# plaits_v10_0603.net
KiCad netlist of a schematic drawn in EAGLE
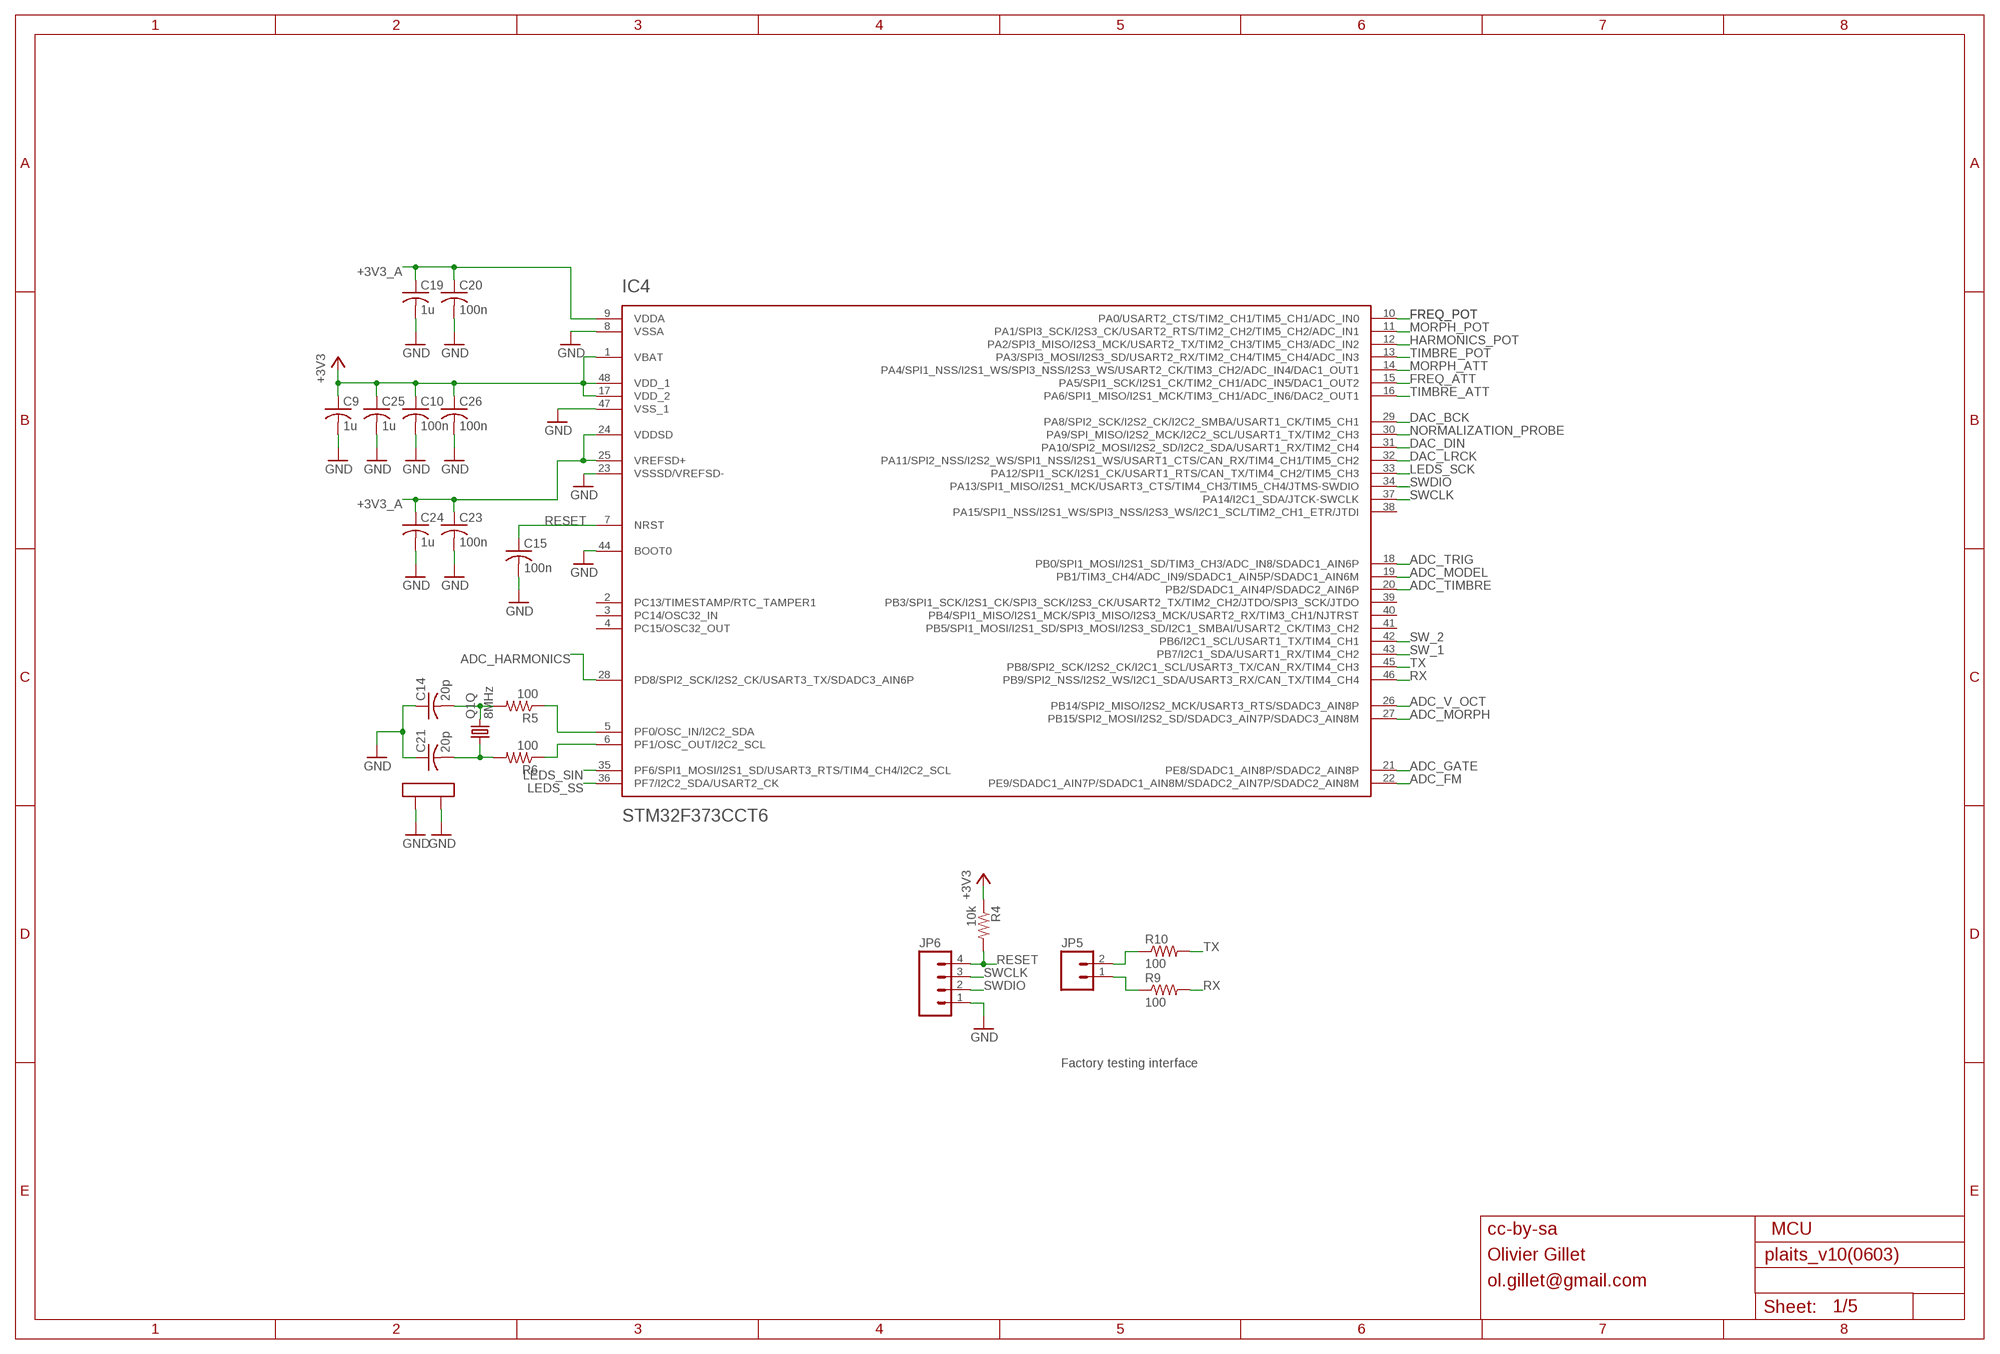
[diagram p0: schematic, sheet 1]
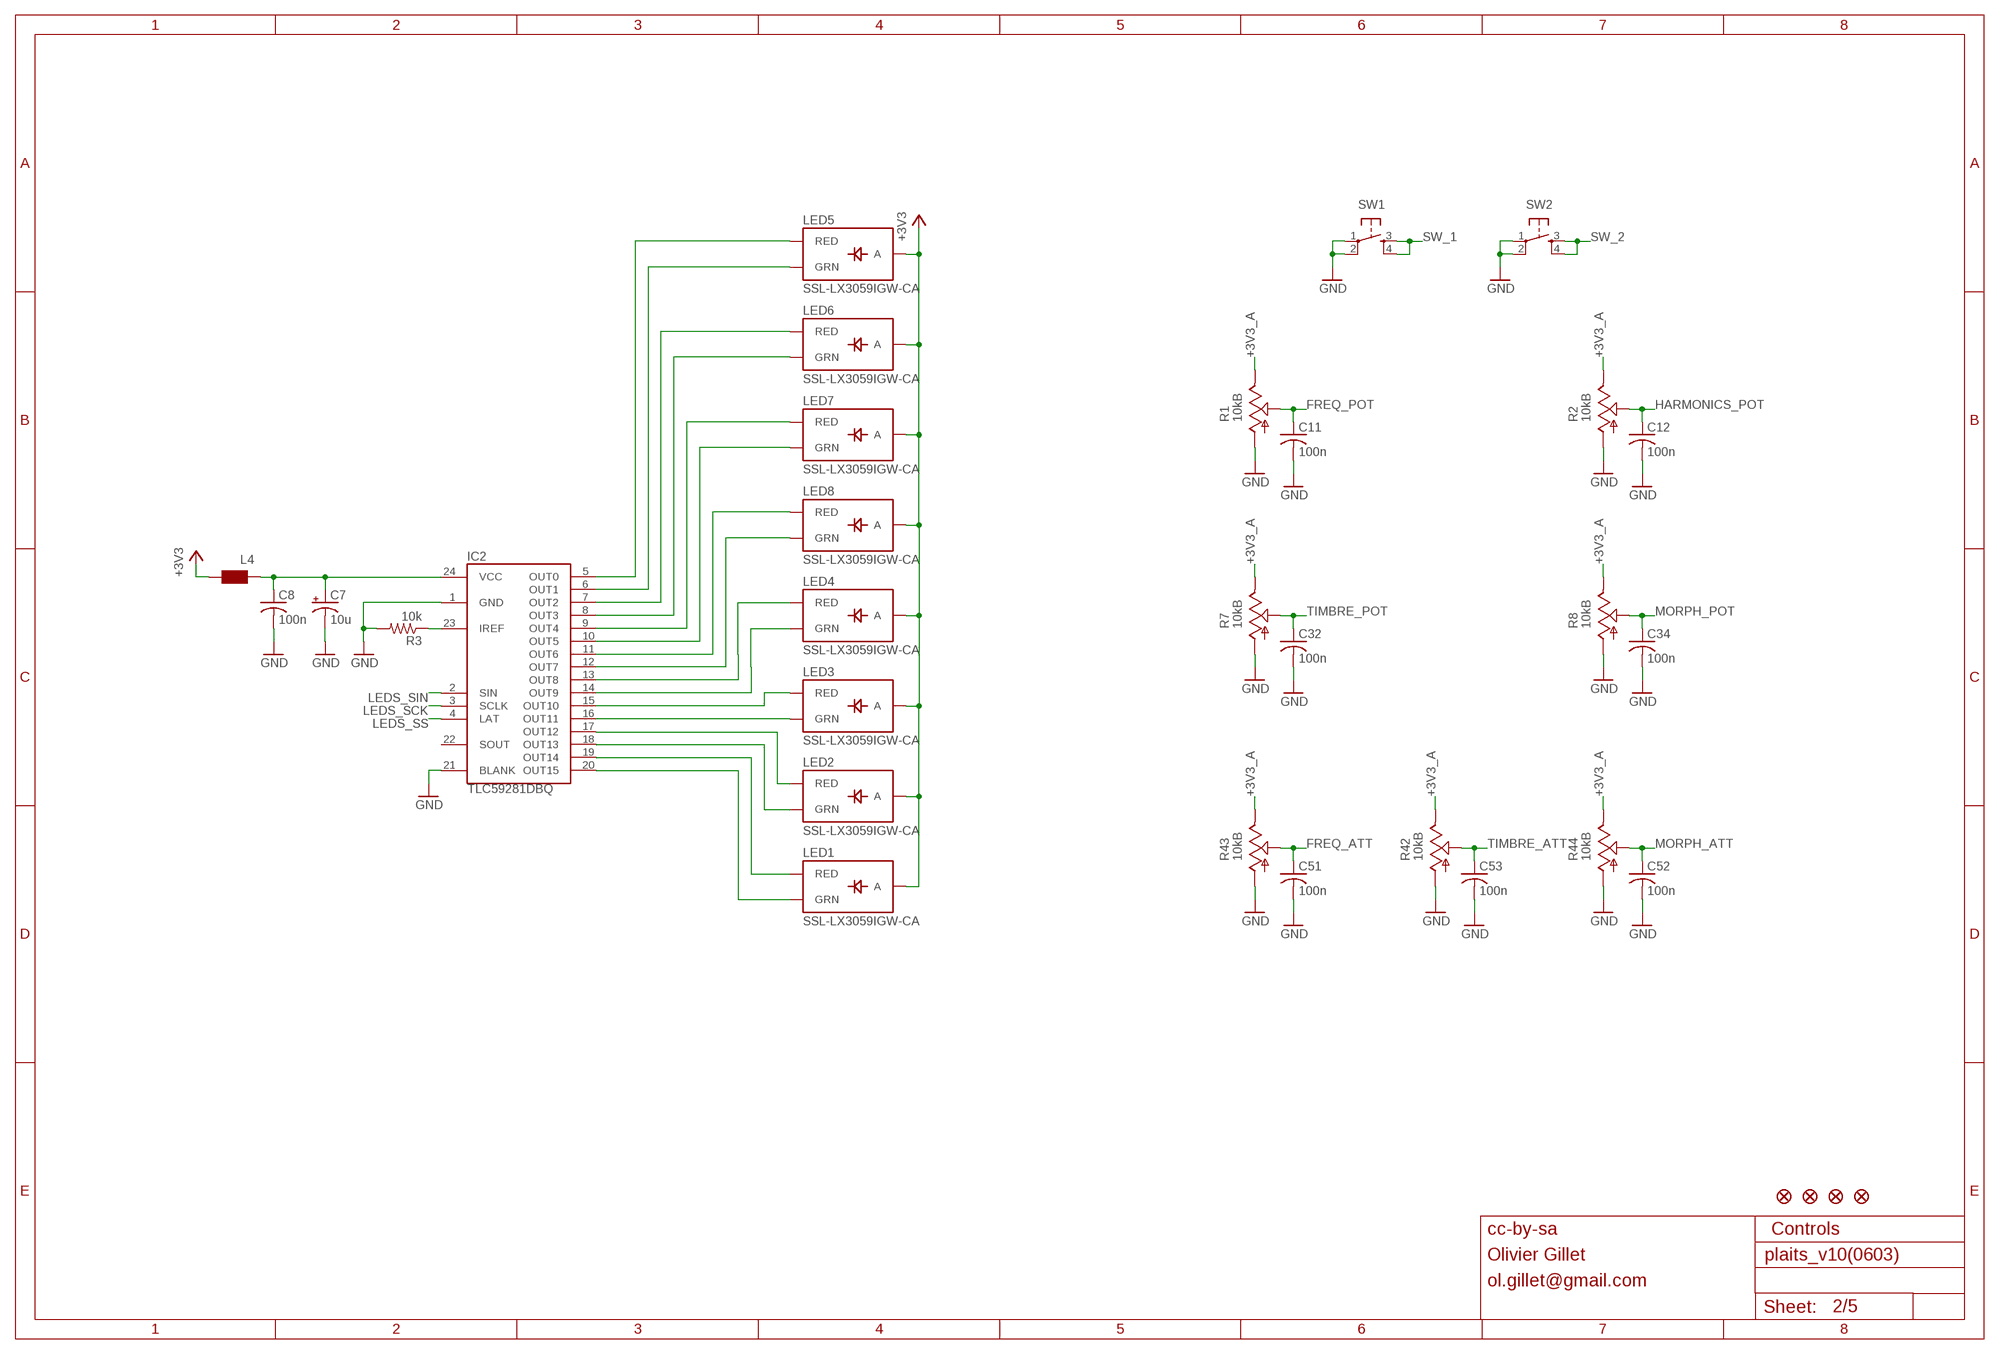
[diagram p1: schematic, sheet 2]
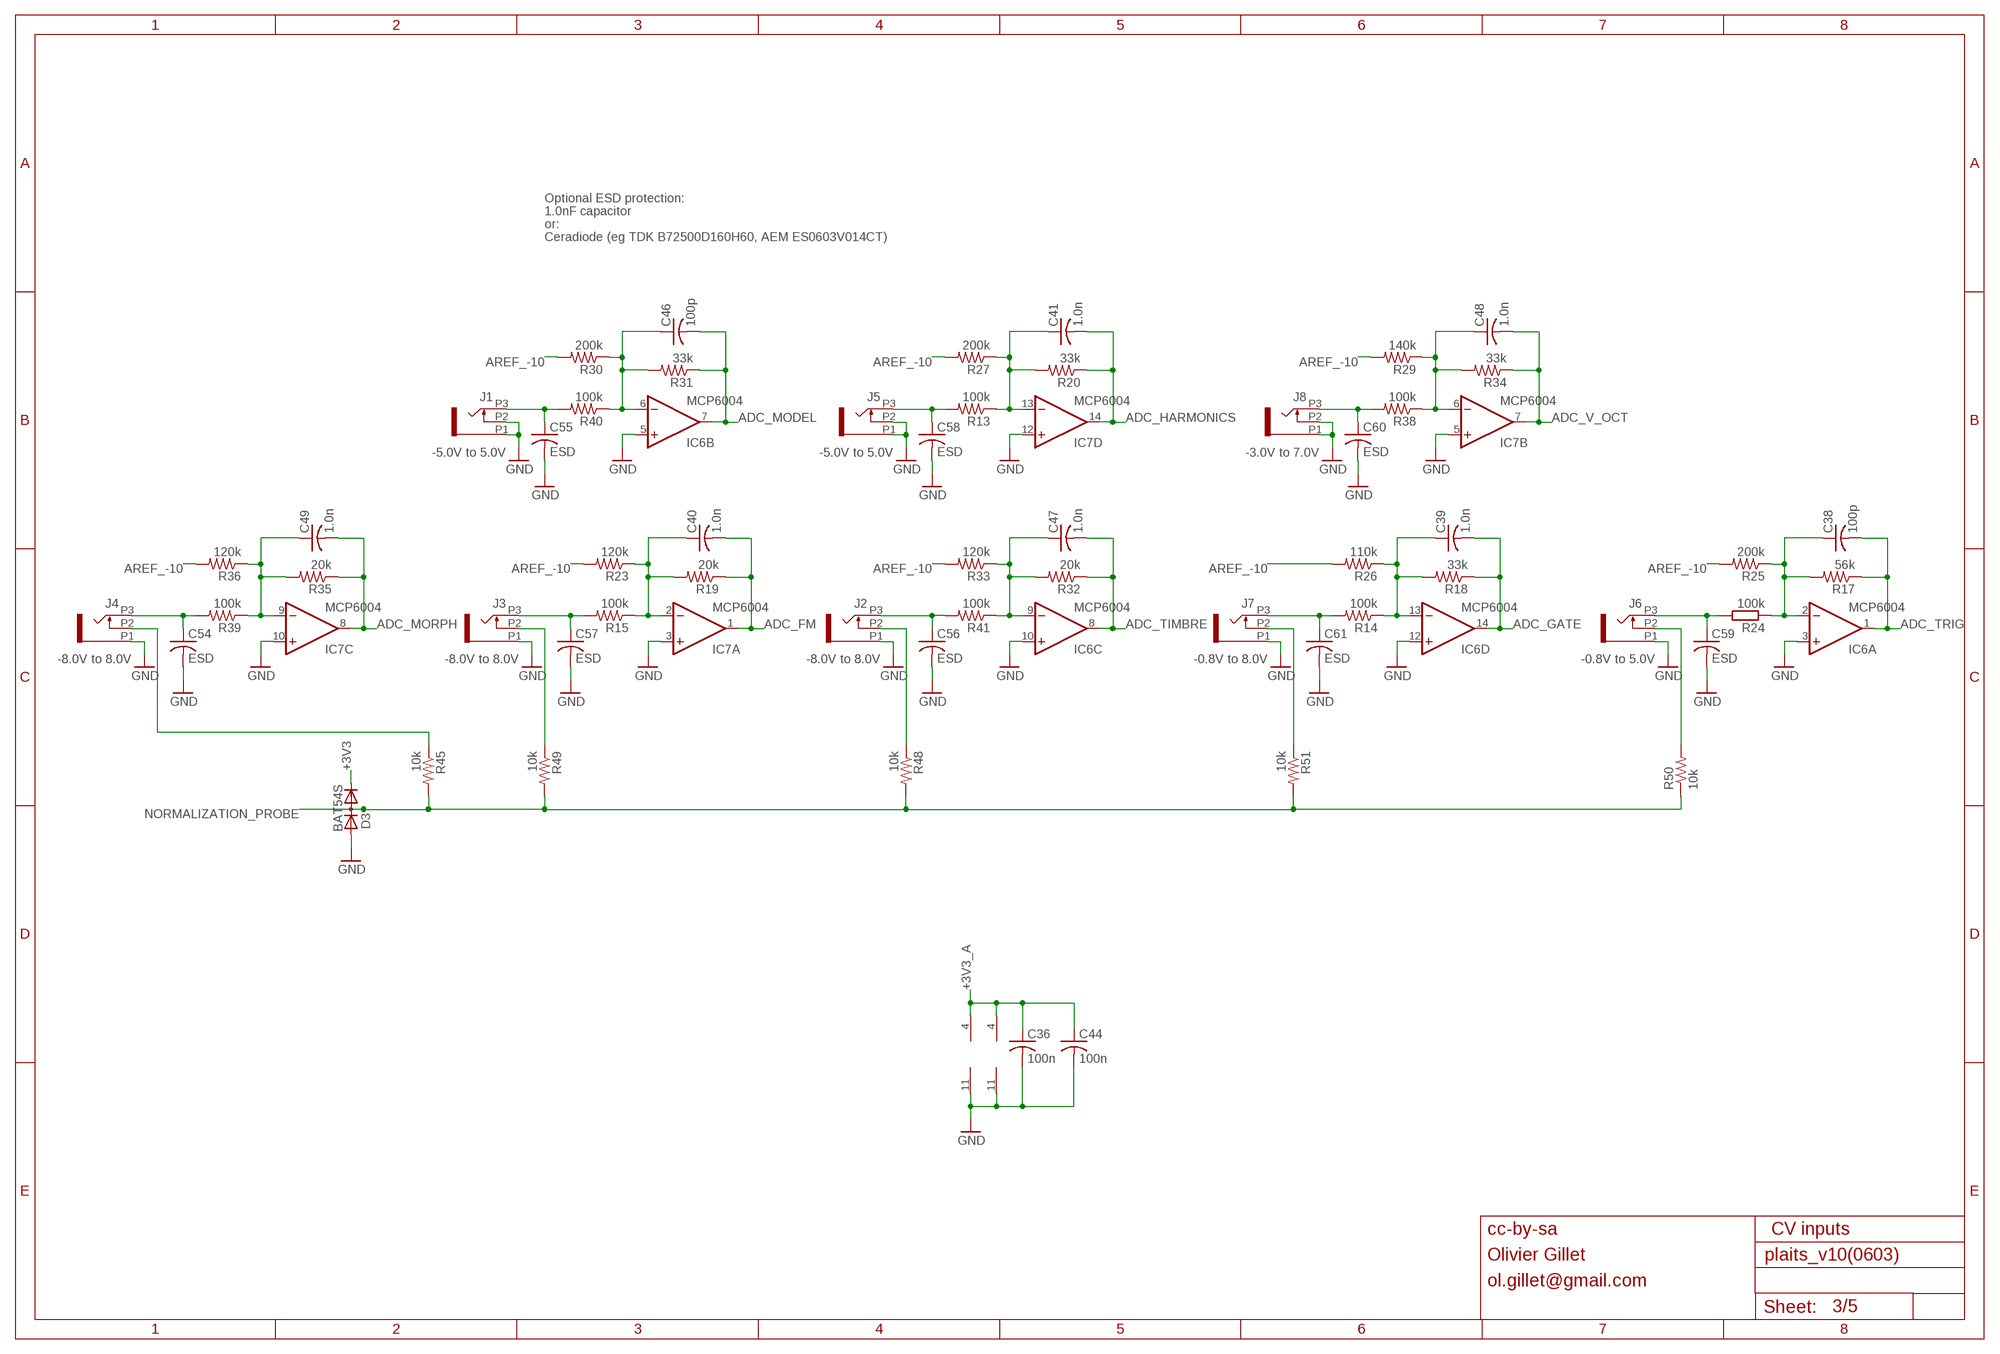
[diagram p2: schematic, sheet 3]
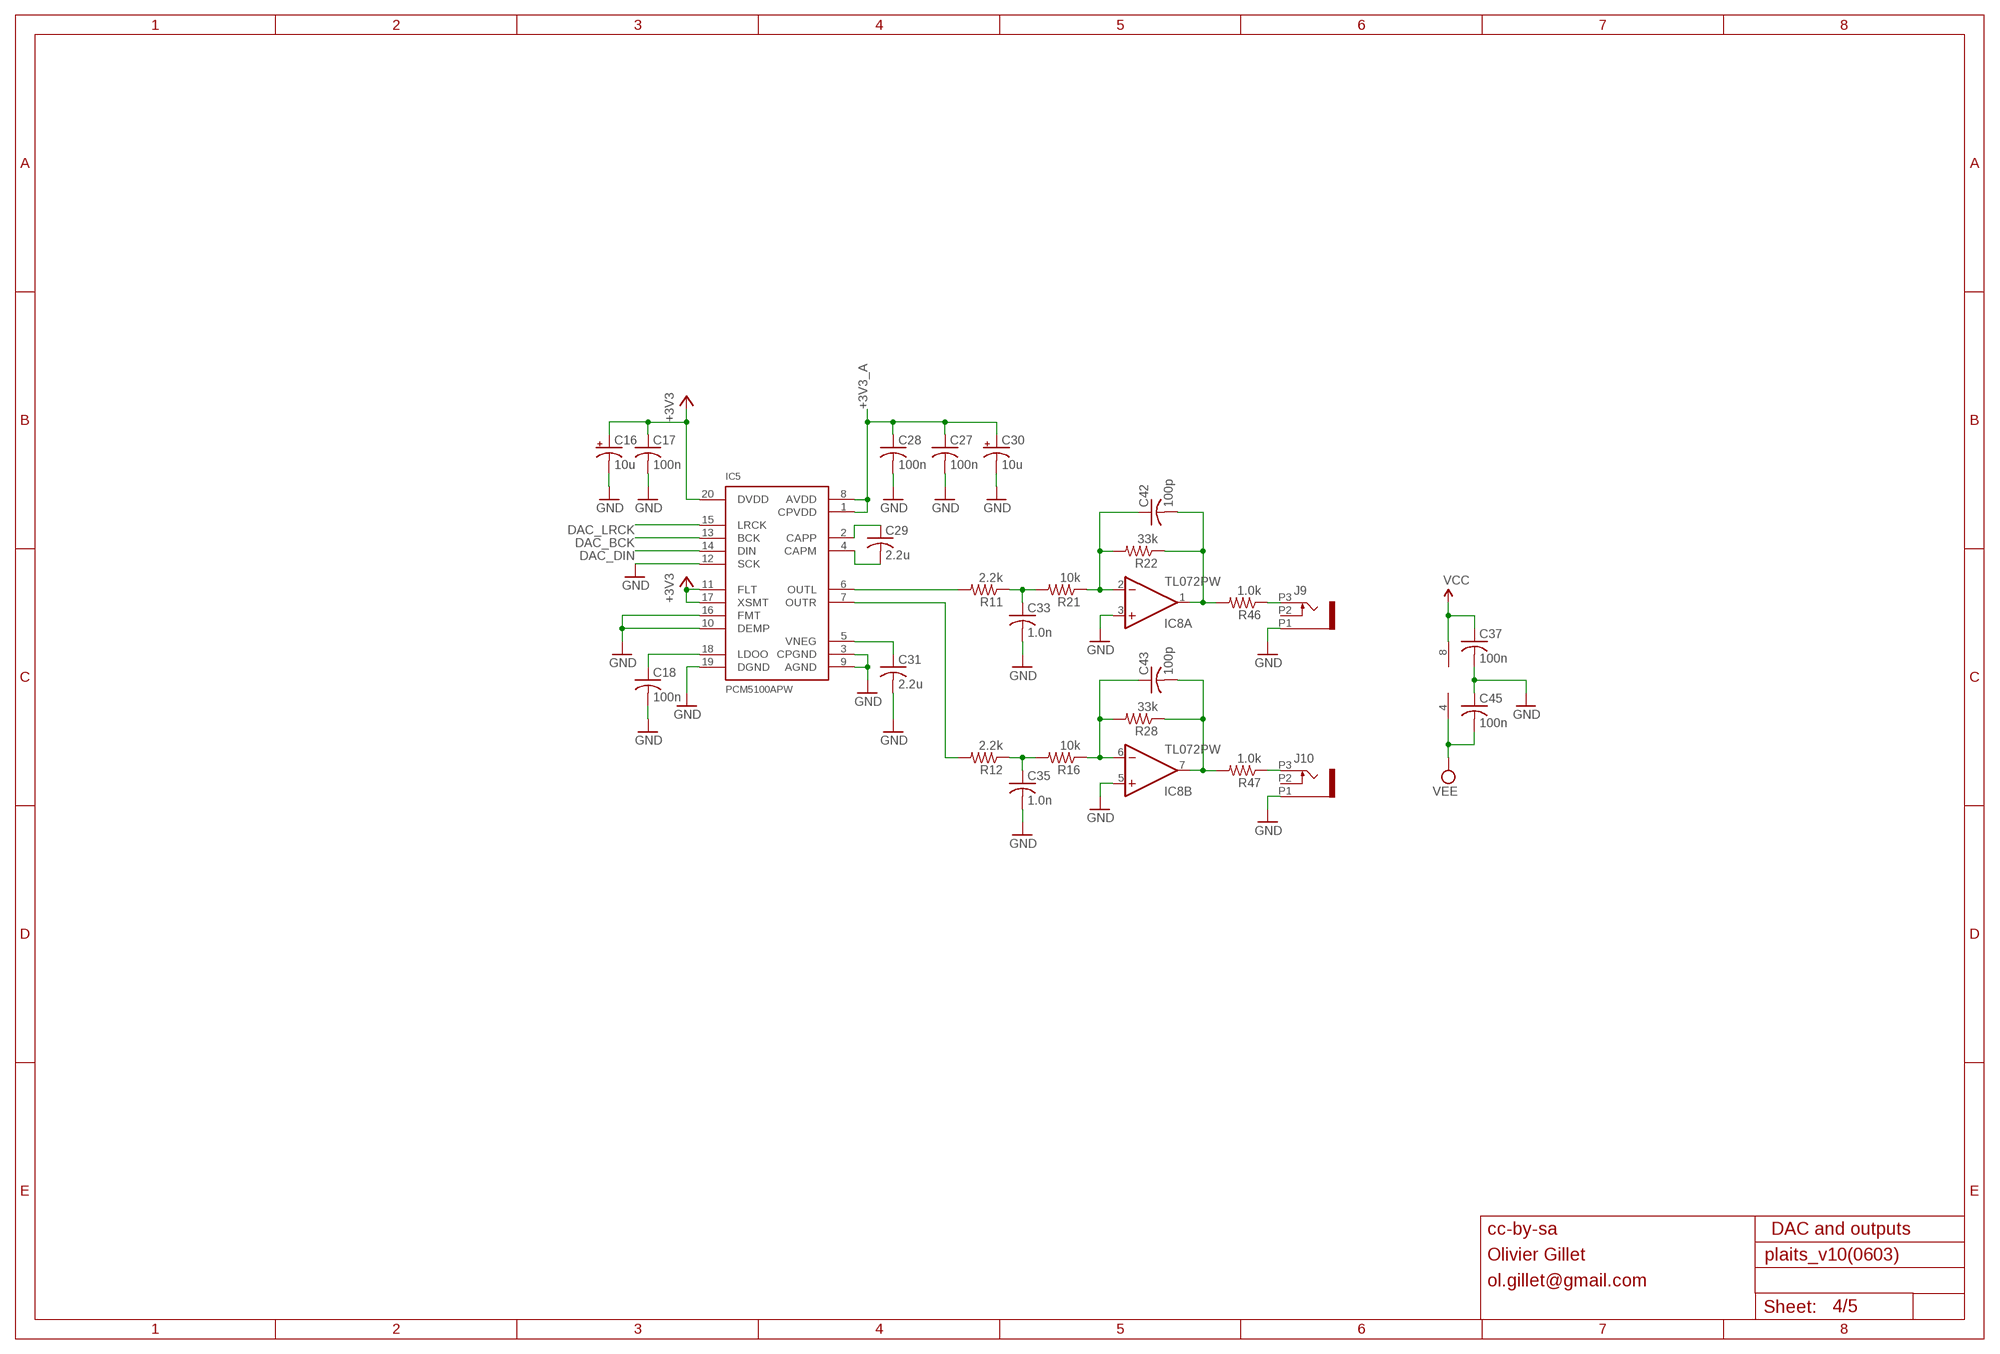
[diagram p3: schematic, sheet 4]
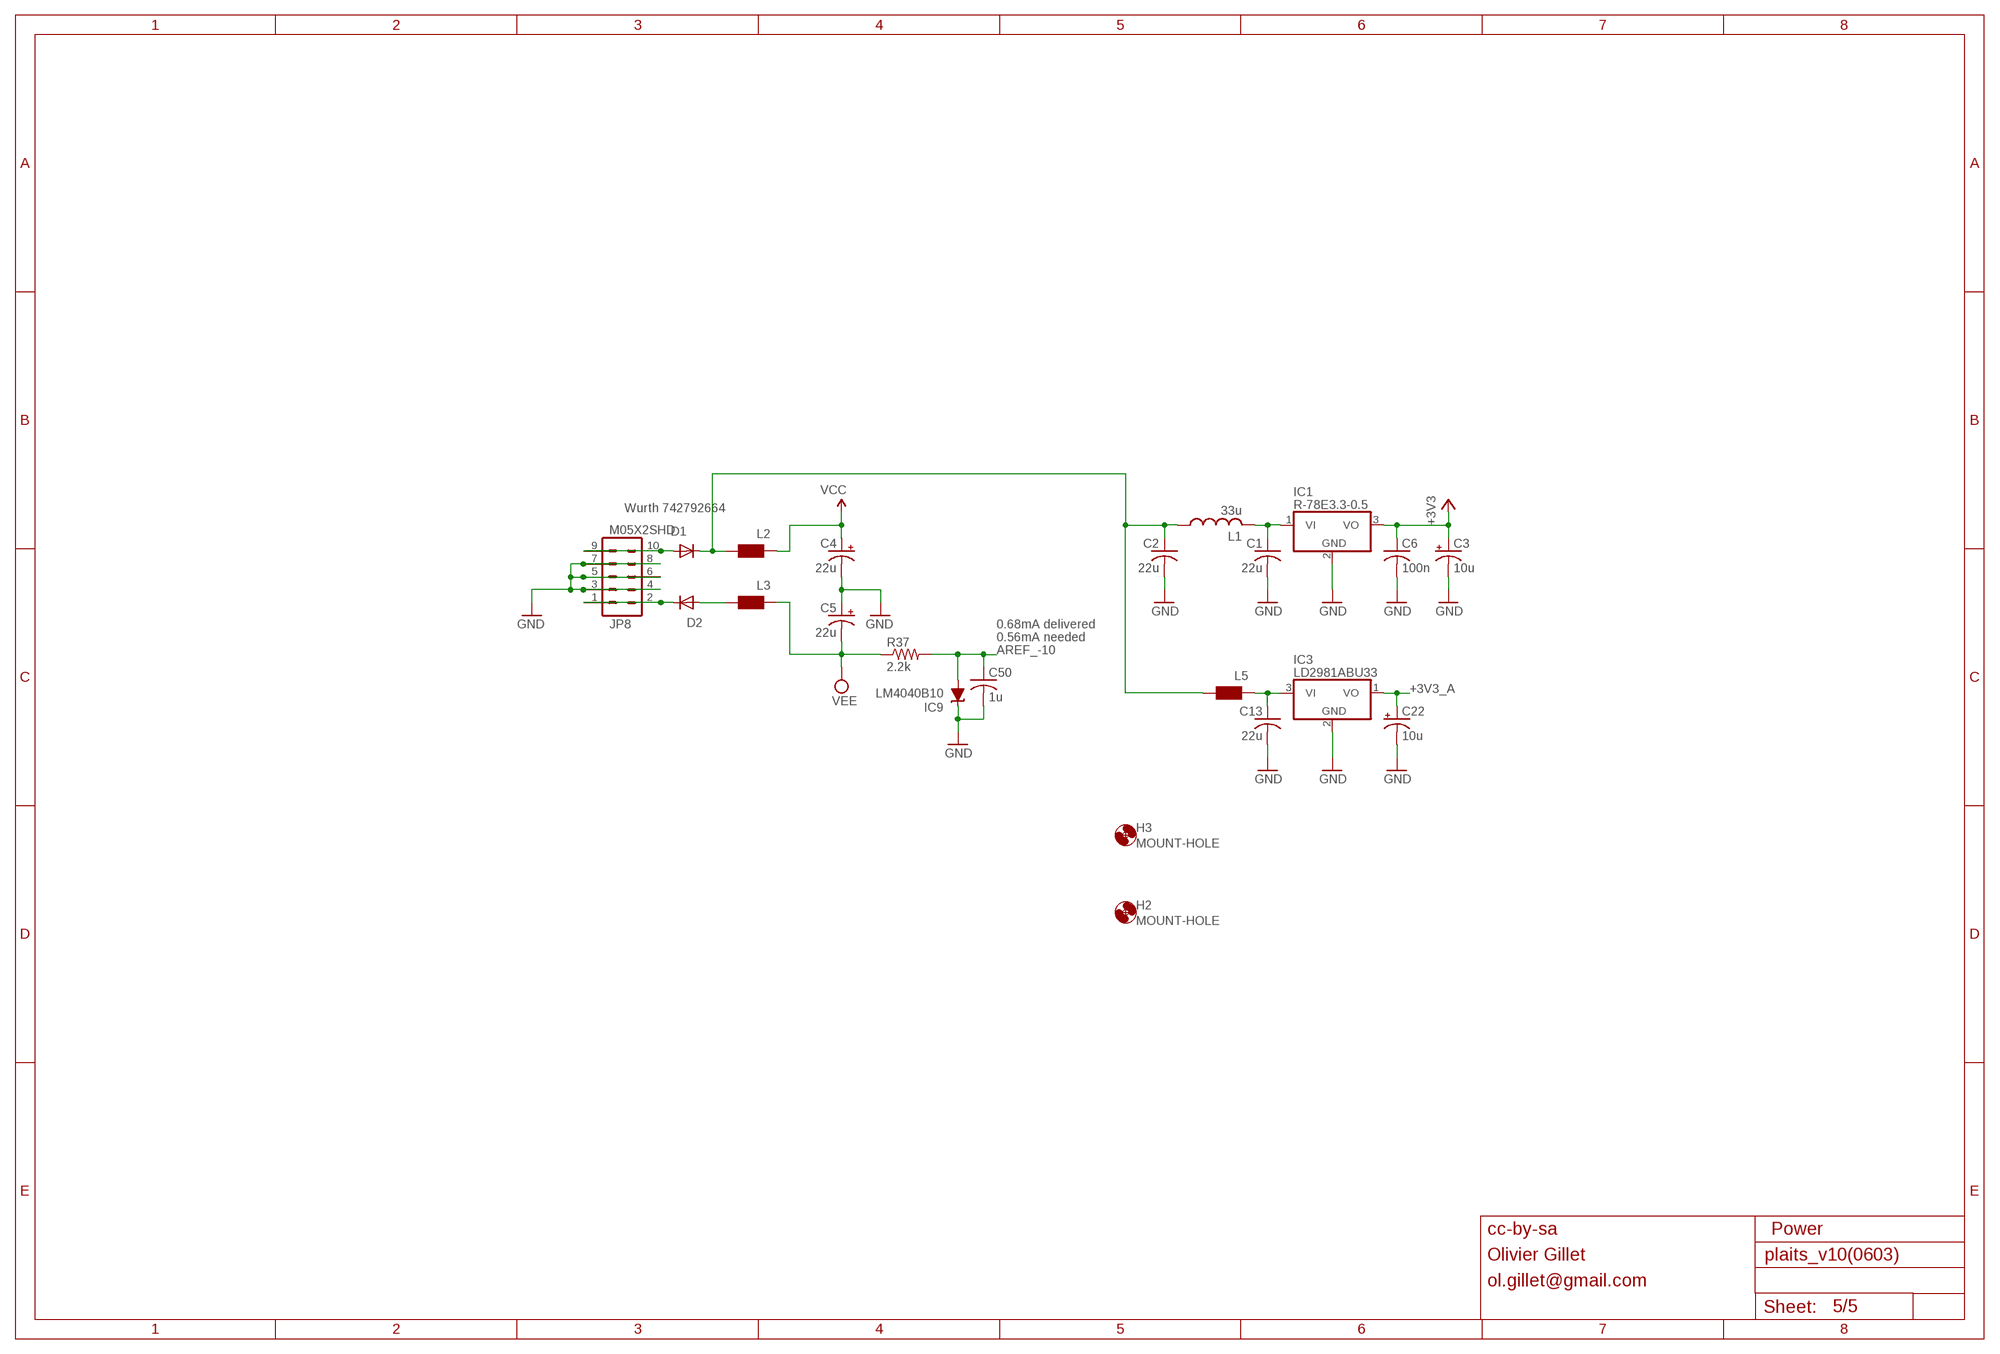
[diagram p4: schematic, sheet 5]

(export (version "E")
  (design (tool "Eeschema 10.0.6"))
  (components
    (comp (ref "C9")
      (value "1u")
      (footprint "eagle-import:C0603")
      (libsource (lib "eagle-import") (part "C-USC0603"))
    )
    (comp (ref "C10")
      (value "100n")
      (footprint "eagle-import:C0603")
      (libsource (lib "eagle-import") (part "C-USC0603"))
    )
    (comp (ref "C14")
      (value "20p")
      (footprint "eagle-import:C0603")
      (libsource (lib "eagle-import") (part "C-USC0603"))
    )
    (comp (ref "C15")
      (value "100n")
      (footprint "eagle-import:C0603")
      (libsource (lib "eagle-import") (part "C-USC0603"))
    )
    (comp (ref "C19")
      (value "1u")
      (footprint "eagle-import:C0603")
      (libsource (lib "eagle-import") (part "C-USC0603"))
    )
    (comp (ref "C20")
      (value "100n")
      (footprint "eagle-import:C0603")
      (libsource (lib "eagle-import") (part "C-USC0603"))
    )
    (comp (ref "C21")
      (value "20p")
      (footprint "eagle-import:C0603")
      (libsource (lib "eagle-import") (part "C-USC0603"))
    )
    (comp (ref "C23")
      (value "100n")
      (footprint "eagle-import:C0603")
      (libsource (lib "eagle-import") (part "C-USC0603"))
    )
    (comp (ref "C24")
      (value "1u")
      (footprint "eagle-import:C0603")
      (libsource (lib "eagle-import") (part "C-USC0603"))
    )
    (comp (ref "C25")
      (value "1u")
      (footprint "eagle-import:C0603")
      (libsource (lib "eagle-import") (part "C-USC0603"))
    )
    (comp (ref "C26")
      (value "100n")
      (footprint "eagle-import:C0603")
      (libsource (lib "eagle-import") (part "C-USC0603"))
    )
    (comp (ref "IC4")
      (value "STM32F373CCT6")
      (footprint "eagle-import:LQFP48")
      (libsource (lib "eagle-import") (part "STM32F373C"))
    )
    (comp (ref "JP5")
      (value "M02PTH")
      (footprint "eagle-import:1X02")
      (libsource (lib "eagle-import") (part "M02PTH"))
    )
    (comp (ref "JP6")
      (value "M04PTH")
      (footprint "eagle-import:1X04")
      (libsource (lib "eagle-import") (part "M04PTH"))
    )
    (comp (ref "Q1")
      (value "8MHz")
      (footprint "eagle-import:CTS406")
      (libsource (lib "eagle-import") (part "CRYSTAL"))
    )
    (comp (ref "R4")
      (value "10k")
      (footprint "eagle-import:R0603")
      (libsource (lib "eagle-import") (part "R-US_R0603"))
    )
    (comp (ref "R5")
      (value "100")
      (footprint "eagle-import:R0603")
      (libsource (lib "eagle-import") (part "R-US_R0603"))
    )
    (comp (ref "R6")
      (value "100")
      (footprint "eagle-import:R0603")
      (libsource (lib "eagle-import") (part "R-US_R0603"))
    )
    (comp (ref "R9")
      (value "100")
      (footprint "eagle-import:R0603")
      (libsource (lib "eagle-import") (part "R-US_R0603"))
    )
    (comp (ref "R10")
      (value "100")
      (footprint "eagle-import:R0603")
      (libsource (lib "eagle-import") (part "R-US_R0603"))
    )
    (comp (ref "C1")
      (value "22u")
      (footprint "eagle-import:C1206")
      (libsource (lib "eagle-import") (part "C-USC1206"))
    )
    (comp (ref "C2")
      (value "22u")
      (footprint "eagle-import:C1206")
      (libsource (lib "eagle-import") (part "C-USC1206"))
    )
    (comp (ref "C3")
      (value "10u")
      (footprint "eagle-import:PANASONIC_A")
      (libsource (lib "eagle-import") (part "CPOL-USA"))
    )
    (comp (ref "C4")
      (value "22u")
      (footprint "eagle-import:PANASONIC_B")
      (libsource (lib "eagle-import") (part "CPOL-USB"))
    )
    (comp (ref "C5")
      (value "22u")
      (footprint "eagle-import:PANASONIC_B")
      (libsource (lib "eagle-import") (part "CPOL-USB"))
    )
    (comp (ref "C6")
      (value "100n")
      (footprint "eagle-import:C0603")
      (libsource (lib "eagle-import") (part "C-USC0603"))
    )
    (comp (ref "C13")
      (value "22u")
      (footprint "eagle-import:C1206")
      (libsource (lib "eagle-import") (part "C-USC1206"))
    )
    (comp (ref "C22")
      (value "10u")
      (footprint "eagle-import:PANASONIC_A")
      (libsource (lib "eagle-import") (part "CPOL-USA"))
    )
    (comp (ref "C50")
      (value "1u")
      (footprint "eagle-import:C0603")
      (libsource (lib "eagle-import") (part "C-USC0603"))
    )
    (comp (ref "D1")
      (value "1N5819HW")
      (footprint "eagle-import:SOD123")
      (libsource (lib "eagle-import") (part "DIODE-SOD123"))
    )
    (comp (ref "D2")
      (value "1N5819HW")
      (footprint "eagle-import:SOD123")
      (libsource (lib "eagle-import") (part "DIODE-SOD123"))
    )
    (comp (ref "H2")
      (value "MOUNT-HOLE")
      (footprint "eagle-import:3,0TINY")
      (libsource (lib "eagle-import") (part "MOUNT-HOLE3.0TINY"))
    )
    (comp (ref "H3")
      (value "MOUNT-HOLE")
      (footprint "eagle-import:3,0TINY")
      (libsource (lib "eagle-import") (part "MOUNT-HOLE3.0TINY"))
    )
    (comp (ref "IC1")
      (value "R-78E3.3-0.5")
      (footprint "eagle-import:WE78")
      (libsource (lib "eagle-import") (part "WE173950378"))
    )
    (comp (ref "IC3")
      (value "LD2981ABU33")
      (footprint "eagle-import:SOT89")
      (libsource (lib "eagle-import") (part "LD2981ABU"))
    )
    (comp (ref "IC9")
      (value "LM4040B10")
      (footprint "eagle-import:DBZ_R-PDSO-G3")
      (libsource (lib "eagle-import") (part "LM4041DBZB12"))
    )
    (comp (ref "JP8")
      (value "M05X2SHD")
      (footprint "eagle-import:2X5-SHROUDED")
      (libsource (lib "eagle-import") (part "M05X2SHD"))
    )
    (comp (ref "L1")
      (value "33u")
      (footprint "eagle-import:L2012C")
      (libsource (lib "eagle-import") (part "L-USL2012C"))
    )
    (comp (ref "L2")
      (value "WE-CBF_0603")
      (footprint "eagle-import:0603")
      (libsource (lib "eagle-import") (part "WE-CBF_0603"))
    )
    (comp (ref "L3")
      (value "WE-CBF_0603")
      (footprint "eagle-import:0603")
      (libsource (lib "eagle-import") (part "WE-CBF_0603"))
    )
    (comp (ref "L5")
      (value "WE-CBF_0603")
      (footprint "eagle-import:0603")
      (libsource (lib "eagle-import") (part "WE-CBF_0603"))
    )
    (comp (ref "R37")
      (value "2.2k")
      (footprint "eagle-import:R0603")
      (libsource (lib "eagle-import") (part "R-US_R0603"))
    )
    (comp (ref "C36")
      (value "100n")
      (footprint "eagle-import:C0402")
      (libsource (lib "eagle-import") (part "C-USC0402"))
    )
    (comp (ref "C38")
      (value "100p")
      (footprint "eagle-import:C0603")
      (libsource (lib "eagle-import") (part "C-USC0603"))
    )
    (comp (ref "C39")
      (value "1.0n")
      (footprint "eagle-import:C0603")
      (libsource (lib "eagle-import") (part "C-USC0603"))
    )
    (comp (ref "C40")
      (value "1.0n")
      (footprint "eagle-import:C0603")
      (libsource (lib "eagle-import") (part "C-USC0603"))
    )
    (comp (ref "C41")
      (value "1.0n")
      (footprint "eagle-import:C0603")
      (libsource (lib "eagle-import") (part "C-USC0603"))
    )
    (comp (ref "C44")
      (value "100n")
      (footprint "eagle-import:C0603")
      (libsource (lib "eagle-import") (part "C-USC0603"))
    )
    (comp (ref "C46")
      (value "100p")
      (footprint "eagle-import:C0603")
      (libsource (lib "eagle-import") (part "C-USC0603"))
    )
    (comp (ref "C47")
      (value "1.0n")
      (footprint "eagle-import:C0603")
      (libsource (lib "eagle-import") (part "C-USC0603"))
    )
    (comp (ref "C48")
      (value "1.0n")
      (footprint "eagle-import:C0603")
      (libsource (lib "eagle-import") (part "C-USC0603"))
    )
    (comp (ref "C49")
      (value "1.0n")
      (footprint "eagle-import:C0603")
      (libsource (lib "eagle-import") (part "C-USC0603"))
    )
    (comp (ref "C54")
      (value "ESD")
      (footprint "eagle-import:C0603K")
      (libsource (lib "eagle-import") (part "C-USC0603K"))
    )
    (comp (ref "C55")
      (value "ESD")
      (footprint "eagle-import:C0603K")
      (libsource (lib "eagle-import") (part "C-USC0603K"))
    )
    (comp (ref "C56")
      (value "ESD")
      (footprint "eagle-import:C0603")
      (libsource (lib "eagle-import") (part "C-USC0603"))
    )
    (comp (ref "C57")
      (value "ESD")
      (footprint "eagle-import:C0603K")
      (libsource (lib "eagle-import") (part "C-USC0603K"))
    )
    (comp (ref "C58")
      (value "ESD")
      (footprint "eagle-import:C0603")
      (libsource (lib "eagle-import") (part "C-USC0603"))
    )
    (comp (ref "C59")
      (value "ESD")
      (footprint "eagle-import:C0603")
      (libsource (lib "eagle-import") (part "C-USC0603"))
    )
    (comp (ref "C60")
      (value "ESD")
      (footprint "eagle-import:C0603")
      (libsource (lib "eagle-import") (part "C-USC0603"))
    )
    (comp (ref "C61")
      (value "ESD")
      (footprint "eagle-import:C0603")
      (libsource (lib "eagle-import") (part "C-USC0603"))
    )
    (comp (ref "D3")
      (value "BAT54S")
      (footprint "eagle-import:SOT23")
      (libsource (lib "eagle-import") (part "DIODE_2CACA-SOT23"))
    )
    (comp (ref "IC6")
      (value "MCP6004")
      (footprint "eagle-import:TSSOP14_065")
      (libsource (lib "eagle-import") (part "TL074PW"))
    )
    (comp (ref "IC7")
      (value "MCP6004")
      (footprint "eagle-import:TSSOP14_065")
      (libsource (lib "eagle-import") (part "TL074PW"))
    )
    (comp (ref "J1")
      (value "PJ301_THONKICONN6")
      (footprint "eagle-import:WQP_PJ_301M6")
      (libsource (lib "eagle-import") (part "PJ301_THONKICONN6"))
    )
    (comp (ref "J2")
      (value "PJ301_THONKICONN6")
      (footprint "eagle-import:WQP_PJ_301M6")
      (libsource (lib "eagle-import") (part "PJ301_THONKICONN6"))
    )
    (comp (ref "J3")
      (value "PJ301_THONKICONN6")
      (footprint "eagle-import:WQP_PJ_301M6")
      (libsource (lib "eagle-import") (part "PJ301_THONKICONN6"))
    )
    (comp (ref "J4")
      (value "PJ301_THONKICONN6")
      (footprint "eagle-import:WQP_PJ_301M6")
      (libsource (lib "eagle-import") (part "PJ301_THONKICONN6"))
    )
    (comp (ref "J5")
      (value "PJ301_THONKICONN6")
      (footprint "eagle-import:WQP_PJ_301M6")
      (libsource (lib "eagle-import") (part "PJ301_THONKICONN6"))
    )
    (comp (ref "J6")
      (value "PJ301_THONKICONN6")
      (footprint "eagle-import:WQP_PJ_301M6")
      (libsource (lib "eagle-import") (part "PJ301_THONKICONN6"))
    )
    (comp (ref "J7")
      (value "PJ301_THONKICONN6")
      (footprint "eagle-import:WQP_PJ_301M6")
      (libsource (lib "eagle-import") (part "PJ301_THONKICONN6"))
    )
    (comp (ref "J8")
      (value "PJ301_THONKICONN6")
      (footprint "eagle-import:WQP_PJ_301M6")
      (libsource (lib "eagle-import") (part "PJ301_THONKICONN6"))
    )
    (comp (ref "R13")
      (value "100k")
      (footprint "eagle-import:R0603")
      (libsource (lib "eagle-import") (part "R-US_R0603"))
    )
    (comp (ref "R14")
      (value "100k")
      (footprint "eagle-import:R0603")
      (libsource (lib "eagle-import") (part "R-US_R0603"))
    )
    (comp (ref "R15")
      (value "100k")
      (footprint "eagle-import:R0603")
      (libsource (lib "eagle-import") (part "R-US_R0603"))
    )
    (comp (ref "R17")
      (value "56k")
      (footprint "eagle-import:R0603")
      (libsource (lib "eagle-import") (part "R-US_R0603"))
    )
    (comp (ref "R18")
      (value "33k")
      (footprint "eagle-import:R0603")
      (libsource (lib "eagle-import") (part "R-US_R0603"))
    )
    (comp (ref "R19")
      (value "20k")
      (footprint "eagle-import:R0603")
      (libsource (lib "eagle-import") (part "R-US_R0603"))
    )
    (comp (ref "R20")
      (value "33k")
      (footprint "eagle-import:R0603")
      (libsource (lib "eagle-import") (part "R-US_R0603"))
    )
    (comp (ref "R23")
      (value "120k")
      (footprint "eagle-import:R0603")
      (libsource (lib "eagle-import") (part "R-US_R0603"))
    )
    (comp (ref "R24")
      (value "100k")
      (footprint "eagle-import:R0603")
      (libsource (lib "eagle-import") (part "R-EU_R0603"))
    )
    (comp (ref "R25")
      (value "200k")
      (footprint "eagle-import:R0603")
      (libsource (lib "eagle-import") (part "R-US_R0603"))
    )
    (comp (ref "R26")
      (value "110k")
      (footprint "eagle-import:R0603")
      (libsource (lib "eagle-import") (part "R-US_R0603"))
    )
    (comp (ref "R27")
      (value "200k")
      (footprint "eagle-import:R0603")
      (libsource (lib "eagle-import") (part "R-US_R0603"))
    )
    (comp (ref "R29")
      (value "140k")
      (footprint "eagle-import:R0603")
      (libsource (lib "eagle-import") (part "R-US_R0603"))
    )
    (comp (ref "R30")
      (value "200k")
      (footprint "eagle-import:R0603")
      (libsource (lib "eagle-import") (part "R-US_R0603"))
    )
    (comp (ref "R31")
      (value "33k")
      (footprint "eagle-import:R0603")
      (libsource (lib "eagle-import") (part "R-US_R0603"))
    )
    (comp (ref "R32")
      (value "20k")
      (footprint "eagle-import:R0603")
      (libsource (lib "eagle-import") (part "R-US_R0603"))
    )
    (comp (ref "R33")
      (value "120k")
      (footprint "eagle-import:R0603")
      (libsource (lib "eagle-import") (part "R-US_R0603"))
    )
    (comp (ref "R34")
      (value "33k")
      (footprint "eagle-import:R0603")
      (libsource (lib "eagle-import") (part "R-US_R0603"))
    )
    (comp (ref "R35")
      (value "20k")
      (footprint "eagle-import:R0603")
      (libsource (lib "eagle-import") (part "R-US_R0603"))
    )
    (comp (ref "R36")
      (value "120k")
      (footprint "eagle-import:R0603")
      (libsource (lib "eagle-import") (part "R-US_R0603"))
    )
    (comp (ref "R38")
      (value "100k")
      (footprint "eagle-import:R0603")
      (libsource (lib "eagle-import") (part "R-US_R0603"))
    )
    (comp (ref "R39")
      (value "100k")
      (footprint "eagle-import:R0603")
      (libsource (lib "eagle-import") (part "R-US_R0603"))
    )
    (comp (ref "R40")
      (value "100k")
      (footprint "eagle-import:R0603")
      (libsource (lib "eagle-import") (part "R-US_R0603"))
    )
    (comp (ref "R41")
      (value "100k")
      (footprint "eagle-import:R0603")
      (libsource (lib "eagle-import") (part "R-US_R0603"))
    )
    (comp (ref "R45")
      (value "10k")
      (footprint "eagle-import:R0603")
      (libsource (lib "eagle-import") (part "R-US_R0603"))
    )
    (comp (ref "R48")
      (value "10k")
      (footprint "eagle-import:R0603")
      (libsource (lib "eagle-import") (part "R-US_R0603"))
    )
    (comp (ref "R49")
      (value "10k")
      (footprint "eagle-import:R0603")
      (libsource (lib "eagle-import") (part "R-US_R0603"))
    )
    (comp (ref "R50")
      (value "10k")
      (footprint "eagle-import:R0603")
      (libsource (lib "eagle-import") (part "R-US_R0603"))
    )
    (comp (ref "R51")
      (value "10k")
      (footprint "eagle-import:R0603")
      (libsource (lib "eagle-import") (part "R-US_R0603"))
    )
    (comp (ref "C7")
      (value "10u")
      (footprint "eagle-import:PANASONIC_A")
      (libsource (lib "eagle-import") (part "CPOL-USA"))
    )
    (comp (ref "C8")
      (value "100n")
      (footprint "eagle-import:C0603")
      (libsource (lib "eagle-import") (part "C-USC0603"))
    )
    (comp (ref "C11")
      (value "100n")
      (footprint "eagle-import:C0603")
      (libsource (lib "eagle-import") (part "C-USC0603"))
    )
    (comp (ref "C12")
      (value "100n")
      (footprint "eagle-import:C0603")
      (libsource (lib "eagle-import") (part "C-USC0603"))
    )
    (comp (ref "C32")
      (value "100n")
      (footprint "eagle-import:C0603")
      (libsource (lib "eagle-import") (part "C-USC0603"))
    )
    (comp (ref "C34")
      (value "100n")
      (footprint "eagle-import:C0603")
      (libsource (lib "eagle-import") (part "C-USC0603"))
    )
    (comp (ref "C51")
      (value "100n")
      (footprint "eagle-import:C0603")
      (libsource (lib "eagle-import") (part "C-USC0603"))
    )
    (comp (ref "C52")
      (value "100n")
      (footprint "eagle-import:C0603")
      (libsource (lib "eagle-import") (part "C-USC0603"))
    )
    (comp (ref "C53")
      (value "100n")
      (footprint "eagle-import:C0603")
      (libsource (lib "eagle-import") (part "C-USC0603"))
    )
    (comp (ref "IC2")
      (value "TLC59281DBQ")
      (footprint "eagle-import:TSSOP24_0635")
      (libsource (lib "eagle-import") (part "TLC59281DBQ"))
    )
    (comp (ref "JP1")
      (value "FIDUCIAL1X2")
      (footprint "eagle-import:FIDUCIAL-1X2")
      (libsource (lib "eagle-import") (part "FIDUCIAL1X2"))
    )
    (comp (ref "JP2")
      (value "FIDUCIAL1X2")
      (footprint "eagle-import:FIDUCIAL-1X2")
      (libsource (lib "eagle-import") (part "FIDUCIAL1X2"))
    )
    (comp (ref "JP3")
      (value "FIDUCIAL1X2")
      (footprint "eagle-import:FIDUCIAL-1X2")
      (libsource (lib "eagle-import") (part "FIDUCIAL1X2"))
    )
    (comp (ref "JP4")
      (value "FIDUCIAL1X2")
      (footprint "eagle-import:FIDUCIAL-1X2")
      (libsource (lib "eagle-import") (part "FIDUCIAL1X2"))
    )
    (comp (ref "L4")
      (value "WE-CBF_0603")
      (footprint "eagle-import:0603")
      (libsource (lib "eagle-import") (part "WE-CBF_0603"))
    )
    (comp (ref "LED1")
      (value "SSL-LX3059IGW-CA")
      (footprint "eagle-import:LED-BICOLOR-THROUGHHOLE-LUMEX")
      (libsource (lib "eagle-import") (part "LED-BICOLOR-THROUGHHOLE-CA"))
    )
    (comp (ref "LED2")
      (value "SSL-LX3059IGW-CA")
      (footprint "eagle-import:LED-BICOLOR-THROUGHHOLE-LUMEX")
      (libsource (lib "eagle-import") (part "LED-BICOLOR-THROUGHHOLE-CA"))
    )
    (comp (ref "LED3")
      (value "SSL-LX3059IGW-CA")
      (footprint "eagle-import:LED-BICOLOR-THROUGHHOLE-LUMEX")
      (libsource (lib "eagle-import") (part "LED-BICOLOR-THROUGHHOLE-CA"))
    )
    (comp (ref "LED4")
      (value "SSL-LX3059IGW-CA")
      (footprint "eagle-import:LED-BICOLOR-THROUGHHOLE-LUMEX")
      (libsource (lib "eagle-import") (part "LED-BICOLOR-THROUGHHOLE-CA"))
    )
    (comp (ref "LED5")
      (value "SSL-LX3059IGW-CA")
      (footprint "eagle-import:LED-BICOLOR-THROUGHHOLE-LUMEX")
      (libsource (lib "eagle-import") (part "LED-BICOLOR-THROUGHHOLE-CA"))
    )
    (comp (ref "LED6")
      (value "SSL-LX3059IGW-CA")
      (footprint "eagle-import:LED-BICOLOR-THROUGHHOLE-LUMEX")
      (libsource (lib "eagle-import") (part "LED-BICOLOR-THROUGHHOLE-CA"))
    )
    (comp (ref "LED7")
      (value "SSL-LX3059IGW-CA")
      (footprint "eagle-import:LED-BICOLOR-THROUGHHOLE-LUMEX")
      (libsource (lib "eagle-import") (part "LED-BICOLOR-THROUGHHOLE-CA"))
    )
    (comp (ref "LED8")
      (value "SSL-LX3059IGW-CA")
      (footprint "eagle-import:LED-BICOLOR-THROUGHHOLE-LUMEX")
      (libsource (lib "eagle-import") (part "LED-BICOLOR-THROUGHHOLE-CA"))
    )
    (comp (ref "R1")
      (value "10kB")
      (footprint "eagle-import:ALPS_POT_VERTICAL_PS")
      (libsource (lib "eagle-import") (part "POT_USVERTICAL_PS"))
    )
    (comp (ref "R2")
      (value "10kB")
      (footprint "eagle-import:ALPS_POT_VERTICAL_PS")
      (libsource (lib "eagle-import") (part "POT_USVERTICAL_PS"))
    )
    (comp (ref "R3")
      (value "10k")
      (footprint "eagle-import:R0603")
      (libsource (lib "eagle-import") (part "R-US_R0603"))
    )
    (comp (ref "R7")
      (value "10kB")
      (footprint "eagle-import:ALPS_POT_VERTICAL_PS")
      (libsource (lib "eagle-import") (part "POT_USVERTICAL_PS"))
    )
    (comp (ref "R8")
      (value "10kB")
      (footprint "eagle-import:ALPS_POT_VERTICAL_PS")
      (libsource (lib "eagle-import") (part "POT_USVERTICAL_PS"))
    )
    (comp (ref "R42")
      (value "10kB")
      (footprint "eagle-import:ALPS_POT_VERTICAL")
      (libsource (lib "eagle-import") (part "POT_USVERTICAL"))
    )
    (comp (ref "R43")
      (value "10kB")
      (footprint "eagle-import:ALPS_POT_VERTICAL")
      (libsource (lib "eagle-import") (part "POT_USVERTICAL"))
    )
    (comp (ref "R44")
      (value "10kB")
      (footprint "eagle-import:ALPS_POT_VERTICAL")
      (libsource (lib "eagle-import") (part "POT_USVERTICAL"))
    )
    (comp (ref "SW1")
      (value "TAC_SWITCHPTH")
      (footprint "eagle-import:TACTILE-PTH")
      (libsource (lib "eagle-import") (part "TAC_SWITCHPTH"))
    )
    (comp (ref "SW2")
      (value "TAC_SWITCHPTH")
      (footprint "eagle-import:TACTILE-PTH")
      (libsource (lib "eagle-import") (part "TAC_SWITCHPTH"))
    )
    (comp (ref "C16")
      (value "10u")
      (footprint "eagle-import:PANASONIC_A")
      (libsource (lib "eagle-import") (part "CPOL-USA"))
    )
    (comp (ref "C17")
      (value "100n")
      (footprint "eagle-import:C0603")
      (libsource (lib "eagle-import") (part "C-USC0603"))
    )
    (comp (ref "C18")
      (value "100n")
      (footprint "eagle-import:C0603")
      (libsource (lib "eagle-import") (part "C-USC0603"))
    )
    (comp (ref "C27")
      (value "100n")
      (footprint "eagle-import:C0603")
      (libsource (lib "eagle-import") (part "C-USC0603"))
    )
    (comp (ref "C28")
      (value "100n")
      (footprint "eagle-import:C0603")
      (libsource (lib "eagle-import") (part "C-USC0603"))
    )
    (comp (ref "C29")
      (value "2.2u")
      (footprint "eagle-import:C0805")
      (libsource (lib "eagle-import") (part "C-USC0805"))
    )
    (comp (ref "C30")
      (value "10u")
      (footprint "eagle-import:PANASONIC_A")
      (libsource (lib "eagle-import") (part "CPOL-USA"))
    )
    (comp (ref "C31")
      (value "2.2u")
      (footprint "eagle-import:C0805")
      (libsource (lib "eagle-import") (part "C-USC0805"))
    )
    (comp (ref "C33")
      (value "1.0n")
      (footprint "eagle-import:C0603")
      (libsource (lib "eagle-import") (part "C-USC0603"))
    )
    (comp (ref "C35")
      (value "1.0n")
      (footprint "eagle-import:C0603")
      (libsource (lib "eagle-import") (part "C-USC0603"))
    )
    (comp (ref "C37")
      (value "100n")
      (footprint "eagle-import:C0603")
      (libsource (lib "eagle-import") (part "C-USC0603"))
    )
    (comp (ref "C42")
      (value "100p")
      (footprint "eagle-import:C0603")
      (libsource (lib "eagle-import") (part "C-USC0603"))
    )
    (comp (ref "C43")
      (value "100p")
      (footprint "eagle-import:C0603")
      (libsource (lib "eagle-import") (part "C-USC0603"))
    )
    (comp (ref "C45")
      (value "100n")
      (footprint "eagle-import:C0603")
      (libsource (lib "eagle-import") (part "C-USC0603"))
    )
    (comp (ref "IC5")
      (value "PCM5100APW")
      (footprint "eagle-import:SSOP20")
      (libsource (lib "eagle-import") (part "PCM5100PW"))
    )
    (comp (ref "IC8")
      (value "TL072PW")
      (footprint "eagle-import:TSSOP08")
      (libsource (lib "eagle-import") (part "TL072PW"))
    )
    (comp (ref "J9")
      (value "PJ301_THONKICONN6")
      (footprint "eagle-import:WQP_PJ_301M6")
      (libsource (lib "eagle-import") (part "PJ301_THONKICONN6"))
    )
    (comp (ref "J10")
      (value "PJ301_THONKICONN6")
      (footprint "eagle-import:WQP_PJ_301M6")
      (libsource (lib "eagle-import") (part "PJ301_THONKICONN6"))
    )
    (comp (ref "R11")
      (value "2.2k")
      (footprint "eagle-import:R0603")
      (libsource (lib "eagle-import") (part "R-US_R0603"))
    )
    (comp (ref "R12")
      (value "2.2k")
      (footprint "eagle-import:R0603")
      (libsource (lib "eagle-import") (part "R-US_R0603"))
    )
    (comp (ref "R16")
      (value "10k")
      (footprint "eagle-import:R0603")
      (libsource (lib "eagle-import") (part "R-US_R0603"))
    )
    (comp (ref "R21")
      (value "10k")
      (footprint "eagle-import:R0603")
      (libsource (lib "eagle-import") (part "R-US_R0603"))
    )
    (comp (ref "R22")
      (value "33k")
      (footprint "eagle-import:R0603")
      (libsource (lib "eagle-import") (part "R-US_R0603"))
    )
    (comp (ref "R28")
      (value "33k")
      (footprint "eagle-import:R0603")
      (libsource (lib "eagle-import") (part "R-US_R0603"))
    )
    (comp (ref "R46")
      (value "1.0k")
      (footprint "eagle-import:R0603")
      (libsource (lib "eagle-import") (part "R-US_R0603"))
    )
    (comp (ref "R47")
      (value "1.0k")
      (footprint "eagle-import:R0603")
      (libsource (lib "eagle-import") (part "R-US_R0603"))
    )
  )
  (nets
    (net (code "1") (name "+3V3") (class "Default")
      (node (ref "C10") (pin "1") (pinfunction "1_1") (pintype "passive"))
      (node (ref "C16") (pin "+") (pinfunction "+_+") (pintype "passive"))
      (node (ref "C17") (pin "1") (pinfunction "1_1") (pintype "passive"))
      (node (ref "C25") (pin "1") (pinfunction "1_1") (pintype "passive"))
      (node (ref "C26") (pin "1") (pinfunction "1_1") (pintype "passive"))
      (node (ref "C3") (pin "+") (pinfunction "+_+") (pintype "passive"))
      (node (ref "C6") (pin "1") (pinfunction "1_1") (pintype "passive"))
      (node (ref "C9") (pin "1") (pinfunction "1_1") (pintype "passive"))
      (node (ref "D3") (pin "2") (pinfunction "C_2") (pintype "passive"))
      (node (ref "IC1") (pin "3") (pinfunction "VO_3") (pintype "passive"))
      (node (ref "IC4") (pin "1") (pinfunction "VBAT_1") (pintype "power_in"))
      (node (ref "IC4") (pin "17") (pinfunction "VDD_2_17") (pintype "power_in"))
      (node (ref "IC4") (pin "48") (pinfunction "VDD_1_48") (pintype "power_in"))
      (node (ref "IC5") (pin "11") (pinfunction "FLT_11") (pintype "input"))
      (node (ref "IC5") (pin "17") (pinfunction "XSMT_17") (pintype "input"))
      (node (ref "IC5") (pin "20") (pinfunction "DVDD_20") (pintype "power_in"))
      (node (ref "L4") (pin "2") (pinfunction "2_2") (pintype "passive"))
      (node (ref "LED1") (pin "A") (pinfunction "A_A") (pintype "bidirectional"))
      (node (ref "LED2") (pin "A") (pinfunction "A_A") (pintype "bidirectional"))
      (node (ref "LED3") (pin "A") (pinfunction "A_A") (pintype "bidirectional"))
      (node (ref "LED4") (pin "A") (pinfunction "A_A") (pintype "bidirectional"))
      (node (ref "LED5") (pin "A") (pinfunction "A_A") (pintype "bidirectional"))
      (node (ref "LED6") (pin "A") (pinfunction "A_A") (pintype "bidirectional"))
      (node (ref "LED7") (pin "A") (pinfunction "A_A") (pintype "bidirectional"))
      (node (ref "LED8") (pin "A") (pinfunction "A_A") (pintype "bidirectional"))
      (node (ref "R4") (pin "1") (pinfunction "1_1") (pintype "passive"))
    )
    (net (code "2") (name "+3V3_A") (class "Default")
      (node (ref "C19") (pin "1") (pinfunction "1_1") (pintype "passive"))
      (node (ref "C20") (pin "1") (pinfunction "1_1") (pintype "passive"))
      (node (ref "C22") (pin "+") (pinfunction "+_+") (pintype "passive"))
      (node (ref "C23") (pin "1") (pinfunction "1_1") (pintype "passive"))
      (node (ref "C24") (pin "1") (pinfunction "1_1") (pintype "passive"))
      (node (ref "C27") (pin "1") (pinfunction "1_1") (pintype "passive"))
      (node (ref "C28") (pin "1") (pinfunction "1_1") (pintype "passive"))
      (node (ref "C30") (pin "+") (pinfunction "+_+") (pintype "passive"))
      (node (ref "C36") (pin "1") (pinfunction "1_1") (pintype "passive"))
      (node (ref "C44") (pin "1") (pinfunction "1_1") (pintype "passive"))
      (node (ref "IC3") (pin "1") (pinfunction "VO_1") (pintype "passive"))
      (node (ref "IC4") (pin "24") (pinfunction "VDDSD_24") (pintype "power_in"))
      (node (ref "IC4") (pin "25") (pinfunction "VREFSD+_25") (pintype "power_in"))
      (node (ref "IC4") (pin "9") (pinfunction "VDDA_9") (pintype "power_in"))
      (node (ref "IC5") (pin "1") (pinfunction "CPVDD_1") (pintype "bidirectional"))
      (node (ref "IC5") (pin "8") (pinfunction "AVDD_8") (pintype "power_in"))
      (node (ref "IC6") (pin "4") (pinfunction "V+_4") (pintype "power_in"))
      (node (ref "IC7") (pin "4") (pinfunction "V+_4") (pintype "power_in"))
      (node (ref "R1") (pin "P$1") (pinfunction "E_P$1") (pintype "passive"))
      (node (ref "R2") (pin "P$1") (pinfunction "E_P$1") (pintype "passive"))
      (node (ref "R42") (pin "P$1") (pinfunction "E_P$1") (pintype "passive"))
      (node (ref "R43") (pin "P$1") (pinfunction "E_P$1") (pintype "passive"))
      (node (ref "R44") (pin "P$1") (pinfunction "E_P$1") (pintype "passive"))
      (node (ref "R7") (pin "P$1") (pinfunction "E_P$1") (pintype "passive"))
      (node (ref "R8") (pin "P$1") (pinfunction "E_P$1") (pintype "passive"))
    )
    (net (code "3") (name "ADC_FM") (class "Default")
      (node (ref "C40") (pin "2") (pinfunction "2_2") (pintype "passive"))
      (node (ref "IC4") (pin "22") (pinfunction "PE9/SDADC1_AIN7P/SDADC1_AIN8M/SDADC2_AIN7P/SDADC2_AIN8M_22") (pintype "bidirectional"))
      (node (ref "IC7") (pin "1") (pinfunction "OUT_1") (pintype "output"))
      (node (ref "R19") (pin "1") (pinfunction "1_1") (pintype "passive"))
    )
    (net (code "4") (name "ADC_GATE") (class "Default")
      (node (ref "C39") (pin "2") (pinfunction "2_2") (pintype "passive"))
      (node (ref "IC4") (pin "21") (pinfunction "PE8/SDADC1_AIN8P/SDADC2_AIN8P_21") (pintype "bidirectional"))
      (node (ref "IC6") (pin "14") (pinfunction "OUT_14") (pintype "output"))
      (node (ref "R18") (pin "1") (pinfunction "1_1") (pintype "passive"))
    )
    (net (code "5") (name "ADC_HARMONICS") (class "Default")
      (node (ref "C41") (pin "2") (pinfunction "2_2") (pintype "passive"))
      (node (ref "IC4") (pin "28") (pinfunction "PD8/SPI2_SCK/I2S2_CK/USART3_TX/SDADC3_AIN6P_28") (pintype "bidirectional"))
      (node (ref "IC7") (pin "14") (pinfunction "OUT_14") (pintype "output"))
      (node (ref "R20") (pin "1") (pinfunction "1_1") (pintype "passive"))
    )
    (net (code "6") (name "ADC_MODEL") (class "Default")
      (node (ref "C46") (pin "2") (pinfunction "2_2") (pintype "passive"))
      (node (ref "IC4") (pin "19") (pinfunction "PB1/TIM3_CH4/ADC_IN9/SDADC1_AIN5P/SDADC1_AIN6M_19") (pintype "bidirectional"))
      (node (ref "IC6") (pin "7") (pinfunction "OUT_7") (pintype "output"))
      (node (ref "R31") (pin "1") (pinfunction "1_1") (pintype "passive"))
    )
    (net (code "7") (name "ADC_MORPH") (class "Default")
      (node (ref "C49") (pin "2") (pinfunction "2_2") (pintype "passive"))
      (node (ref "IC4") (pin "27") (pinfunction "PB15/SPI2_MOSI/I2S2_SD/SDADC3_AIN7P/SDADC3_AIN8M_27") (pintype "bidirectional"))
      (node (ref "IC7") (pin "8") (pinfunction "OUT_8") (pintype "output"))
      (node (ref "R35") (pin "1") (pinfunction "1_1") (pintype "passive"))
    )
    (net (code "8") (name "ADC_TIMBRE") (class "Default")
      (node (ref "C47") (pin "2") (pinfunction "2_2") (pintype "passive"))
      (node (ref "IC4") (pin "20") (pinfunction "PB2/SDADC1_AIN4P/SDADC2_AIN6P_20") (pintype "bidirectional"))
      (node (ref "IC6") (pin "8") (pinfunction "OUT_8") (pintype "output"))
      (node (ref "R32") (pin "1") (pinfunction "1_1") (pintype "passive"))
    )
    (net (code "9") (name "ADC_TRIG") (class "Default")
      (node (ref "C38") (pin "2") (pinfunction "2_2") (pintype "passive"))
      (node (ref "IC4") (pin "18") (pinfunction "PB0/SPI1_MOSI/I2S1_SD/TIM3_CH3/ADC_IN8/SDADC1_AIN6P_18") (pintype "bidirectional"))
      (node (ref "IC6") (pin "1") (pinfunction "OUT_1") (pintype "output"))
      (node (ref "R17") (pin "1") (pinfunction "1_1") (pintype "passive"))
    )
    (net (code "10") (name "ADC_V_OCT") (class "Default")
      (node (ref "C48") (pin "2") (pinfunction "2_2") (pintype "passive"))
      (node (ref "IC4") (pin "26") (pinfunction "PB14/SPI2_MISO/I2S2_MCK/USART3_RTS/SDADC3_AIN8P_26") (pintype "bidirectional"))
      (node (ref "IC7") (pin "7") (pinfunction "OUT_7") (pintype "output"))
      (node (ref "R34") (pin "1") (pinfunction "1_1") (pintype "passive"))
    )
    (net (code "11") (name "AREF_-10") (class "Default")
      (node (ref "C50") (pin "1") (pinfunction "1_1") (pintype "passive"))
      (node (ref "IC9") (pin "2") (pinfunction "A_2") (pintype "passive"))
      (node (ref "R23") (pin "2") (pinfunction "2_2") (pintype "passive"))
      (node (ref "R25") (pin "2") (pinfunction "2_2") (pintype "passive"))
      (node (ref "R26") (pin "2") (pinfunction "2_2") (pintype "passive"))
      (node (ref "R27") (pin "2") (pinfunction "2_2") (pintype "passive"))
      (node (ref "R29") (pin "2") (pinfunction "2_2") (pintype "passive"))
      (node (ref "R30") (pin "2") (pinfunction "2_2") (pintype "passive"))
      (node (ref "R33") (pin "2") (pinfunction "2_2") (pintype "passive"))
      (node (ref "R36") (pin "2") (pinfunction "2_2") (pintype "passive"))
      (node (ref "R37") (pin "2") (pinfunction "2_2") (pintype "passive"))
    )
    (net (code "12") (name "DAC_BCK") (class "Default")
      (node (ref "IC4") (pin "29") (pinfunction "PA8/SPI2_SCK/I2S2_CK/I2C2_SMBA/USART1_CK/TIM5_CH1_29") (pintype "bidirectional"))
      (node (ref "IC5") (pin "13") (pinfunction "BCK_13") (pintype "input"))
    )
    (net (code "13") (name "DAC_DIN") (class "Default")
      (node (ref "IC4") (pin "31") (pinfunction "PA10/SPI2_MOSI/I2S2_SD/I2C2_SDA/USART1_RX/TIM2_CH4_31") (pintype "bidirectional"))
      (node (ref "IC5") (pin "14") (pinfunction "DIN_14") (pintype "input"))
    )
    (net (code "14") (name "DAC_LRCK") (class "Default")
      (node (ref "IC4") (pin "32") (pinfunction "PA11/SPI2_NSS/I2S2_WS/SPI1_NSS/I2S1_WS/USART1_CTS/CAN_RX/TIM4_CH1/TIM5_CH2_32") (pintype "bidirectional"))
      (node (ref "IC5") (pin "15") (pinfunction "LRCK_15") (pintype "input"))
    )
    (net (code "15") (name "FREQ_ATT") (class "Default")
      (node (ref "C51") (pin "1") (pinfunction "1_1") (pintype "passive"))
      (node (ref "IC4") (pin "15") (pinfunction "PA5/SPI1_SCK/I2S1_CK/TIM2_CH1/ADC_IN5/DAC1_OUT2_15") (pintype "bidirectional"))
      (node (ref "R43") (pin "P$2") (pinfunction "S_P$2") (pintype "passive"))
    )
    (net (code "16") (name "FREQ_POT") (class "Default")
      (node (ref "C11") (pin "1") (pinfunction "1_1") (pintype "passive"))
      (node (ref "IC4") (pin "10") (pinfunction "PA0/USART2_CTS/TIM2_CH1/TIM5_CH1/ADC_IN0_10") (pintype "bidirectional"))
      (node (ref "R1") (pin "P$2") (pinfunction "S_P$2") (pintype "passive"))
    )
    (net (code "17") (name "GND") (class "Default")
      (node (ref "C1") (pin "2") (pinfunction "2_2") (pintype "passive"))
      (node (ref "C10") (pin "2") (pinfunction "2_2") (pintype "passive"))
      (node (ref "C11") (pin "2") (pinfunction "2_2") (pintype "passive"))
      (node (ref "C12") (pin "2") (pinfunction "2_2") (pintype "passive"))
      (node (ref "C13") (pin "2") (pinfunction "2_2") (pintype "passive"))
      (node (ref "C14") (pin "1") (pinfunction "1_1") (pintype "passive"))
      (node (ref "C15") (pin "2") (pinfunction "2_2") (pintype "passive"))
      (node (ref "C16") (pin "-") (pinfunction "-_-") (pintype "passive"))
      (node (ref "C17") (pin "2") (pinfunction "2_2") (pintype "passive"))
      (node (ref "C18") (pin "2") (pinfunction "2_2") (pintype "passive"))
      (node (ref "C19") (pin "2") (pinfunction "2_2") (pintype "passive"))
      (node (ref "C2") (pin "2") (pinfunction "2_2") (pintype "passive"))
      (node (ref "C20") (pin "2") (pinfunction "2_2") (pintype "passive"))
      (node (ref "C21") (pin "1") (pinfunction "1_1") (pintype "passive"))
      (node (ref "C22") (pin "-") (pinfunction "-_-") (pintype "passive"))
      (node (ref "C23") (pin "2") (pinfunction "2_2") (pintype "passive"))
      (node (ref "C24") (pin "2") (pinfunction "2_2") (pintype "passive"))
      (node (ref "C25") (pin "2") (pinfunction "2_2") (pintype "passive"))
      (node (ref "C26") (pin "2") (pinfunction "2_2") (pintype "passive"))
      (node (ref "C27") (pin "2") (pinfunction "2_2") (pintype "passive"))
      (node (ref "C28") (pin "2") (pinfunction "2_2") (pintype "passive"))
      (node (ref "C3") (pin "-") (pinfunction "-_-") (pintype "passive"))
      (node (ref "C30") (pin "-") (pinfunction "-_-") (pintype "passive"))
      (node (ref "C31") (pin "2") (pinfunction "2_2") (pintype "passive"))
      (node (ref "C32") (pin "2") (pinfunction "2_2") (pintype "passive"))
      (node (ref "C33") (pin "2") (pinfunction "2_2") (pintype "passive"))
      (node (ref "C34") (pin "2") (pinfunction "2_2") (pintype "passive"))
      (node (ref "C35") (pin "2") (pinfunction "2_2") (pintype "passive"))
      (node (ref "C36") (pin "2") (pinfunction "2_2") (pintype "passive"))
      (node (ref "C37") (pin "2") (pinfunction "2_2") (pintype "passive"))
      (node (ref "C4") (pin "-") (pinfunction "-_-") (pintype "passive"))
      (node (ref "C44") (pin "2") (pinfunction "2_2") (pintype "passive"))
      (node (ref "C45") (pin "1") (pinfunction "1_1") (pintype "passive"))
      (node (ref "C5") (pin "+") (pinfunction "+_+") (pintype "passive"))
      (node (ref "C50") (pin "2") (pinfunction "2_2") (pintype "passive"))
      (node (ref "C51") (pin "2") (pinfunction "2_2") (pintype "passive"))
      (node (ref "C52") (pin "2") (pinfunction "2_2") (pintype "passive"))
      (node (ref "C53") (pin "2") (pinfunction "2_2") (pintype "passive"))
      (node (ref "C54") (pin "2") (pinfunction "2_2") (pintype "passive"))
      (node (ref "C55") (pin "2") (pinfunction "2_2") (pintype "passive"))
      (node (ref "C56") (pin "2") (pinfunction "2_2") (pintype "passive"))
      (node (ref "C57") (pin "2") (pinfunction "2_2") (pintype "passive"))
      (node (ref "C58") (pin "2") (pinfunction "2_2") (pintype "passive"))
      (node (ref "C59") (pin "2") (pinfunction "2_2") (pintype "passive"))
      (node (ref "C6") (pin "2") (pinfunction "2_2") (pintype "passive"))
      (node (ref "C60") (pin "2") (pinfunction "2_2") (pintype "passive"))
      (node (ref "C61") (pin "2") (pinfunction "2_2") (pintype "passive"))
      (node (ref "C7") (pin "-") (pinfunction "-_-") (pintype "passive"))
      (node (ref "C8") (pin "2") (pinfunction "2_2") (pintype "passive"))
      (node (ref "C9") (pin "2") (pinfunction "2_2") (pintype "passive"))
      (node (ref "D3") (pin "1") (pinfunction "A_1") (pintype "passive"))
      (node (ref "IC1") (pin "2") (pinfunction "GND_2") (pintype "passive"))
      (node (ref "IC2") (pin "1") (pinfunction "GND_1") (pintype "bidirectional"))
      (node (ref "IC2") (pin "21") (pinfunction "BLANK_21") (pintype "bidirectional"))
      (node (ref "IC3") (pin "2") (pinfunction "GND_2") (pintype "passive"))
      (node (ref "IC4") (pin "23") (pinfunction "VSSSD/VREFSD-_23") (pintype "power_in"))
      (node (ref "IC4") (pin "44") (pinfunction "BOOT0_44") (pintype "bidirectional"))
      (node (ref "IC4") (pin "47") (pinfunction "VSS_1_47") (pintype "power_in"))
      (node (ref "IC4") (pin "8") (pinfunction "VSSA_8") (pintype "power_in"))
      (node (ref "IC5") (pin "10") (pinfunction "DEMP_10") (pintype "input"))
      (node (ref "IC5") (pin "12") (pinfunction "SCK_12") (pintype "input"))
      (node (ref "IC5") (pin "16") (pinfunction "FMT_16") (pintype "input"))
      (node (ref "IC5") (pin "19") (pinfunction "DGND_19") (pintype "power_in"))
      (node (ref "IC5") (pin "3") (pinfunction "CPGND_3") (pintype "bidirectional"))
      (node (ref "IC5") (pin "9") (pinfunction "AGND_9") (pintype "power_in"))
      (node (ref "IC6") (pin "10") (pinfunction "+IN_10") (pintype "input"))
      (node (ref "IC6") (pin "11") (pinfunction "V-_11") (pintype "power_in"))
      (node (ref "IC6") (pin "12") (pinfunction "+IN_12") (pintype "input"))
      (node (ref "IC6") (pin "3") (pinfunction "+IN_3") (pintype "input"))
      (node (ref "IC6") (pin "5") (pinfunction "+IN_5") (pintype "input"))
      (node (ref "IC7") (pin "10") (pinfunction "+IN_10") (pintype "input"))
      (node (ref "IC7") (pin "11") (pinfunction "V-_11") (pintype "power_in"))
      (node (ref "IC7") (pin "12") (pinfunction "+IN_12") (pintype "input"))
      (node (ref "IC7") (pin "3") (pinfunction "+IN_3") (pintype "input"))
      (node (ref "IC7") (pin "5") (pinfunction "+IN_5") (pintype "input"))
      (node (ref "IC8") (pin "3") (pinfunction "+IN_3") (pintype "input"))
      (node (ref "IC8") (pin "5") (pinfunction "+IN_5") (pintype "input"))
      (node (ref "IC9") (pin "1") (pinfunction "C_1") (pintype "passive"))
      (node (ref "J1") (pin "P1") (pinfunction "1_P1") (pintype "passive"))
      (node (ref "J1") (pin "P2") (pinfunction "2_P2") (pintype "passive"))
      (node (ref "J10") (pin "P1") (pinfunction "1_P1") (pintype "passive"))
      (node (ref "J2") (pin "P1") (pinfunction "1_P1") (pintype "passive"))
      (node (ref "J3") (pin "P1") (pinfunction "1_P1") (pintype "passive"))
      (node (ref "J4") (pin "P1") (pinfunction "1_P1") (pintype "passive"))
      (node (ref "J5") (pin "P1") (pinfunction "1_P1") (pintype "passive"))
      (node (ref "J5") (pin "P2") (pinfunction "2_P2") (pintype "passive"))
      (node (ref "J6") (pin "P1") (pinfunction "1_P1") (pintype "passive"))
      (node (ref "J7") (pin "P1") (pinfunction "1_P1") (pintype "passive"))
      (node (ref "J8") (pin "P1") (pinfunction "1_P1") (pintype "passive"))
      (node (ref "J8") (pin "P2") (pinfunction "2_P2") (pintype "passive"))
      (node (ref "J9") (pin "P1") (pinfunction "1_P1") (pintype "passive"))
      (node (ref "JP6") (pin "1") (pinfunction "1_1") (pintype "passive"))
      (node (ref "JP8") (pin "3") (pinfunction "3_3") (pintype "passive"))
      (node (ref "JP8") (pin "4") (pinfunction "4_4") (pintype "passive"))
      (node (ref "JP8") (pin "5") (pinfunction "5_5") (pintype "passive"))
      (node (ref "JP8") (pin "6") (pinfunction "6_6") (pintype "passive"))
      (node (ref "JP8") (pin "7") (pinfunction "7_7") (pintype "passive"))
      (node (ref "JP8") (pin "8") (pinfunction "8_8") (pintype "passive"))
      (node (ref "Q1") (pin "2") (pinfunction "LID1_2") (pintype "power_in"))
      (node (ref "Q1") (pin "4") (pinfunction "LID2_4") (pintype "power_in"))
      (node (ref "R1") (pin "P$3") (pinfunction "A_P$3") (pintype "passive"))
      (node (ref "R2") (pin "P$3") (pinfunction "A_P$3") (pintype "passive"))
      (node (ref "R3") (pin "2") (pinfunction "2_2") (pintype "passive"))
      (node (ref "R42") (pin "P$3") (pinfunction "A_P$3") (pintype "passive"))
      (node (ref "R43") (pin "P$3") (pinfunction "A_P$3") (pintype "passive"))
      (node (ref "R44") (pin "P$3") (pinfunction "A_P$3") (pintype "passive"))
      (node (ref "R7") (pin "P$3") (pinfunction "A_P$3") (pintype "passive"))
      (node (ref "R8") (pin "P$3") (pinfunction "A_P$3") (pintype "passive"))
      (node (ref "SW1") (pin "1") (pinfunction "1_1") (pintype "passive"))
      (node (ref "SW1") (pin "2") (pinfunction "2_2") (pintype "passive"))
      (node (ref "SW2") (pin "1") (pinfunction "1_1") (pintype "passive"))
      (node (ref "SW2") (pin "2") (pinfunction "2_2") (pintype "passive"))
    )
    (net (code "18") (name "HARMONICS_POT") (class "Default")
      (node (ref "C12") (pin "1") (pinfunction "1_1") (pintype "passive"))
      (node (ref "IC4") (pin "12") (pinfunction "PA2/SPI3_MISO/I2S3_MCK/USART2_TX/TIM2_CH3/TIM5_CH3/ADC_IN2_12") (pintype "bidirectional"))
      (node (ref "R2") (pin "P$2") (pinfunction "S_P$2") (pintype "passive"))
    )
    (net (code "19") (name "LEDS_SCK") (class "Default")
      (node (ref "IC2") (pin "3") (pinfunction "SCLK_3") (pintype "bidirectional"))
      (node (ref "IC4") (pin "33") (pinfunction "PA12/SPI1_SCK/I2S1_CK/USART1_RTS/CAN_TX/TIM4_CH2/TIM5_CH3_33") (pintype "bidirectional"))
    )
    (net (code "20") (name "LEDS_SIN") (class "Default")
      (node (ref "IC2") (pin "2") (pinfunction "SIN_2") (pintype "bidirectional"))
      (node (ref "IC4") (pin "35") (pinfunction "PF6/SPI1_MOSI/I2S1_SD/USART3_RTS/TIM4_CH4/I2C2_SCL_35") (pintype "bidirectional"))
    )
    (net (code "21") (name "LEDS_SS") (class "Default")
      (node (ref "IC2") (pin "4") (pinfunction "LAT_4") (pintype "bidirectional"))
      (node (ref "IC4") (pin "36") (pinfunction "PF7/I2C2_SDA/USART2_CK_36") (pintype "bidirectional"))
    )
    (net (code "22") (name "MORPH_ATT") (class "Default")
      (node (ref "C52") (pin "1") (pinfunction "1_1") (pintype "passive"))
      (node (ref "IC4") (pin "14") (pinfunction "PA4/SPI1_NSS/I2S1_WS/SPI3_NSS/I2S3_WS/USART2_CK/TIM3_CH2/ADC_IN4/DAC1_OUT1_14") (pintype "bidirectional"))
      (node (ref "R44") (pin "P$2") (pinfunction "S_P$2") (pintype "passive"))
    )
    (net (code "23") (name "MORPH_POT") (class "Default")
      (node (ref "C34") (pin "1") (pinfunction "1_1") (pintype "passive"))
      (node (ref "IC4") (pin "11") (pinfunction "PA1/SPI3_SCK/I2S3_CK/USART2_RTS/TIM2_CH2/TIM5_CH2/ADC_IN1_11") (pintype "bidirectional"))
      (node (ref "R8") (pin "P$2") (pinfunction "S_P$2") (pintype "passive"))
    )
    (net (code "24") (name "NORMALIZATION_PROBE") (class "Default")
      (node (ref "D3") (pin "3") (pinfunction "AC_3") (pintype "passive"))
      (node (ref "IC4") (pin "30") (pinfunction "PA9/SPI_MISO/I2S2_MCK/I2C2_SCL/USART1_TX/TIM2_CH3_30") (pintype "bidirectional"))
      (node (ref "R45") (pin "2") (pinfunction "2_2") (pintype "passive"))
      (node (ref "R48") (pin "2") (pinfunction "2_2") (pintype "passive"))
      (node (ref "R49") (pin "2") (pinfunction "2_2") (pintype "passive"))
      (node (ref "R50") (pin "1") (pinfunction "1_1") (pintype "passive"))
      (node (ref "R51") (pin "2") (pinfunction "2_2") (pintype "passive"))
    )
    (net (code "25") (name "Net-(C2-Pad1)") (class "Default")
      (node (ref "C2") (pin "1") (pinfunction "1_1") (pintype "passive"))
      (node (ref "D1") (pin "C") (pinfunction "C_C") (pintype "passive"))
      (node (ref "L1") (pin "1") (pinfunction "1_1") (pintype "passive"))
      (node (ref "L2") (pin "2") (pinfunction "2_2") (pintype "passive"))
      (node (ref "L5") (pin "2") (pinfunction "2_2") (pintype "passive"))
    )
    (net (code "26") (name "Net-(C21-Pad2)") (class "Default")
      (node (ref "C21") (pin "2") (pinfunction "2_2") (pintype "passive"))
      (node (ref "Q1") (pin "1") (pinfunction "1_1") (pintype "passive"))
      (node (ref "R6") (pin "2") (pinfunction "2_2") (pintype "passive"))
    )
    (net (code "27") (name "Net-(C33-Pad1)") (class "Default")
      (node (ref "C33") (pin "1") (pinfunction "1_1") (pintype "passive"))
      (node (ref "R11") (pin "1") (pinfunction "1_1") (pintype "passive"))
      (node (ref "R21") (pin "2") (pinfunction "2_2") (pintype "passive"))
    )
    (net (code "28") (name "Net-(C35-Pad1)") (class "Default")
      (node (ref "C35") (pin "1") (pinfunction "1_1") (pintype "passive"))
      (node (ref "R12") (pin "1") (pinfunction "1_1") (pintype "passive"))
      (node (ref "R16") (pin "2") (pinfunction "2_2") (pintype "passive"))
    )
    (net (code "29") (name "Net-(D1-PadA)") (class "Default")
      (node (ref "D1") (pin "A") (pinfunction "A_A") (pintype "passive"))
      (node (ref "JP8") (pin "10") (pinfunction "10_10") (pintype "passive"))
      (node (ref "JP8") (pin "9") (pinfunction "9_9") (pintype "passive"))
    )
    (net (code "30") (name "Net-(D2-PadA)") (class "Default")
      (node (ref "D2") (pin "A") (pinfunction "A_A") (pintype "passive"))
      (node (ref "L3") (pin "2") (pinfunction "2_2") (pintype "passive"))
    )
    (net (code "31") (name "Net-(D2-PadC)") (class "Default")
      (node (ref "D2") (pin "C") (pinfunction "C_C") (pintype "passive"))
      (node (ref "JP8") (pin "1") (pinfunction "1_1") (pintype "passive"))
      (node (ref "JP8") (pin "2") (pinfunction "2_2") (pintype "passive"))
    )
    (net (code "32") (name "Net-(IC1-VI)") (class "Default")
      (node (ref "C1") (pin "1") (pinfunction "1_1") (pintype "passive"))
      (node (ref "IC1") (pin "1") (pinfunction "VI_1") (pintype "input"))
      (node (ref "L1") (pin "2") (pinfunction "2_2") (pintype "passive"))
    )
    (net (code "33") (name "Net-(IC2-IREF)") (class "Default")
      (node (ref "IC2") (pin "23") (pinfunction "IREF_23") (pintype "bidirectional"))
      (node (ref "R3") (pin "1") (pinfunction "1_1") (pintype "passive"))
    )
    (net (code "34") (name "Net-(IC2-OUT0)") (class "Default")
      (node (ref "IC2") (pin "5") (pinfunction "OUT0_5") (pintype "bidirectional"))
      (node (ref "LED5") (pin "RED_C") (pinfunction "RED_RED_C") (pintype "bidirectional"))
    )
    (net (code "35") (name "Net-(IC2-OUT1)") (class "Default")
      (node (ref "IC2") (pin "6") (pinfunction "OUT1_6") (pintype "bidirectional"))
      (node (ref "LED5") (pin "GREEN_C") (pinfunction "GRN_GREEN_C") (pintype "bidirectional"))
    )
    (net (code "36") (name "Net-(IC2-OUT2)") (class "Default")
      (node (ref "IC2") (pin "7") (pinfunction "OUT2_7") (pintype "bidirectional"))
      (node (ref "LED6") (pin "RED_C") (pinfunction "RED_RED_C") (pintype "bidirectional"))
    )
    (net (code "37") (name "Net-(IC2-OUT3)") (class "Default")
      (node (ref "IC2") (pin "8") (pinfunction "OUT3_8") (pintype "bidirectional"))
      (node (ref "LED6") (pin "GREEN_C") (pinfunction "GRN_GREEN_C") (pintype "bidirectional"))
    )
    (net (code "38") (name "Net-(IC2-OUT4)") (class "Default")
      (node (ref "IC2") (pin "9") (pinfunction "OUT4_9") (pintype "bidirectional"))
      (node (ref "LED7") (pin "RED_C") (pinfunction "RED_RED_C") (pintype "bidirectional"))
    )
    (net (code "39") (name "Net-(IC2-OUT5)") (class "Default")
      (node (ref "IC2") (pin "10") (pinfunction "OUT5_10") (pintype "bidirectional"))
      (node (ref "LED7") (pin "GREEN_C") (pinfunction "GRN_GREEN_C") (pintype "bidirectional"))
    )
    (net (code "40") (name "Net-(IC2-OUT6)") (class "Default")
      (node (ref "IC2") (pin "11") (pinfunction "OUT6_11") (pintype "bidirectional"))
      (node (ref "LED8") (pin "RED_C") (pinfunction "RED_RED_C") (pintype "bidirectional"))
    )
    (net (code "41") (name "Net-(IC2-OUT7)") (class "Default")
      (node (ref "IC2") (pin "12") (pinfunction "OUT7_12") (pintype "bidirectional"))
      (node (ref "LED8") (pin "GREEN_C") (pinfunction "GRN_GREEN_C") (pintype "bidirectional"))
    )
    (net (code "42") (name "Net-(IC2-OUT8)") (class "Default")
      (node (ref "IC2") (pin "13") (pinfunction "OUT8_13") (pintype "bidirectional"))
      (node (ref "LED4") (pin "RED_C") (pinfunction "RED_RED_C") (pintype "bidirectional"))
    )
    (net (code "43") (name "Net-(IC2-OUT9)") (class "Default")
      (node (ref "IC2") (pin "14") (pinfunction "OUT9_14") (pintype "bidirectional"))
      (node (ref "LED4") (pin "GREEN_C") (pinfunction "GRN_GREEN_C") (pintype "bidirectional"))
    )
    (net (code "44") (name "Net-(IC2-OUT10)") (class "Default")
      (node (ref "IC2") (pin "15") (pinfunction "OUT10_15") (pintype "bidirectional"))
      (node (ref "LED3") (pin "RED_C") (pinfunction "RED_RED_C") (pintype "bidirectional"))
    )
    (net (code "45") (name "Net-(IC2-OUT11)") (class "Default")
      (node (ref "IC2") (pin "16") (pinfunction "OUT11_16") (pintype "bidirectional"))
      (node (ref "LED3") (pin "GREEN_C") (pinfunction "GRN_GREEN_C") (pintype "bidirectional"))
    )
    (net (code "46") (name "Net-(IC2-OUT12)") (class "Default")
      (node (ref "IC2") (pin "17") (pinfunction "OUT12_17") (pintype "bidirectional"))
      (node (ref "LED2") (pin "RED_C") (pinfunction "RED_RED_C") (pintype "bidirectional"))
    )
    (net (code "47") (name "Net-(IC2-OUT13)") (class "Default")
      (node (ref "IC2") (pin "18") (pinfunction "OUT13_18") (pintype "bidirectional"))
      (node (ref "LED2") (pin "GREEN_C") (pinfunction "GRN_GREEN_C") (pintype "bidirectional"))
    )
    (net (code "48") (name "Net-(IC2-OUT14)") (class "Default")
      (node (ref "IC2") (pin "19") (pinfunction "OUT14_19") (pintype "bidirectional"))
      (node (ref "LED1") (pin "RED_C") (pinfunction "RED_RED_C") (pintype "bidirectional"))
    )
    (net (code "49") (name "Net-(IC2-OUT15)") (class "Default")
      (node (ref "IC2") (pin "20") (pinfunction "OUT15_20") (pintype "bidirectional"))
      (node (ref "LED1") (pin "GREEN_C") (pinfunction "GRN_GREEN_C") (pintype "bidirectional"))
    )
    (net (code "50") (name "Net-(IC2-VCC)") (class "Default")
      (node (ref "C7") (pin "+") (pinfunction "+_+") (pintype "passive"))
      (node (ref "C8") (pin "1") (pinfunction "1_1") (pintype "passive"))
      (node (ref "IC2") (pin "24") (pinfunction "VCC_24") (pintype "bidirectional"))
      (node (ref "L4") (pin "1") (pinfunction "1_1") (pintype "passive"))
    )
    (net (code "51") (name "Net-(IC3-VI)") (class "Default")
      (node (ref "C13") (pin "1") (pinfunction "1_1") (pintype "passive"))
      (node (ref "IC3") (pin "3") (pinfunction "VI_3") (pintype "input"))
      (node (ref "L5") (pin "1") (pinfunction "1_1") (pintype "passive"))
    )
    (net (code "52") (name "Net-(IC4-PF0{slash}OSC_IN{slash}I2C2_SDA)") (class "Default")
      (node (ref "IC4") (pin "5") (pinfunction "PF0/OSC_IN/I2C2_SDA_5") (pintype "bidirectional"))
      (node (ref "R5") (pin "1") (pinfunction "1_1") (pintype "passive"))
    )
    (net (code "53") (name "Net-(IC4-PF1{slash}OSC_OUT{slash}I2C2_SCL)") (class "Default")
      (node (ref "IC4") (pin "6") (pinfunction "PF1/OSC_OUT/I2C2_SCL_6") (pintype "bidirectional"))
      (node (ref "R6") (pin "1") (pinfunction "1_1") (pintype "passive"))
    )
    (net (code "54") (name "Net-(IC5-CAPM)") (class "Default")
      (node (ref "C29") (pin "2") (pinfunction "2_2") (pintype "passive"))
      (node (ref "IC5") (pin "4") (pinfunction "CAPM_4") (pintype "bidirectional"))
    )
    (net (code "55") (name "Net-(IC5-CAPP)") (class "Default")
      (node (ref "C29") (pin "1") (pinfunction "1_1") (pintype "passive"))
      (node (ref "IC5") (pin "2") (pinfunction "CAPP_2") (pintype "bidirectional"))
    )
    (net (code "56") (name "Net-(IC5-LDOO)") (class "Default")
      (node (ref "C18") (pin "1") (pinfunction "1_1") (pintype "passive"))
      (node (ref "IC5") (pin "18") (pinfunction "LDOO_18") (pintype "bidirectional"))
    )
    (net (code "57") (name "Net-(IC5-OUTL)") (class "Default")
      (node (ref "IC5") (pin "6") (pinfunction "OUTL_6") (pintype "output"))
      (node (ref "R11") (pin "2") (pinfunction "2_2") (pintype "passive"))
    )
    (net (code "58") (name "Net-(IC5-OUTR)") (class "Default")
      (node (ref "IC5") (pin "7") (pinfunction "OUTR_7") (pintype "output"))
      (node (ref "R12") (pin "2") (pinfunction "2_2") (pintype "passive"))
    )
    (net (code "59") (name "Net-(IC5-VNEG)") (class "Default")
      (node (ref "C31") (pin "1") (pinfunction "1_1") (pintype "passive"))
      (node (ref "IC5") (pin "5") (pinfunction "VNEG_5") (pintype "input"))
    )
    (net (code "60") (name "Net-(IC6A--IN)") (class "Default")
      (node (ref "C38") (pin "1") (pinfunction "1_1") (pintype "passive"))
      (node (ref "IC6") (pin "2") (pinfunction "-IN_2") (pintype "input"))
      (node (ref "R17") (pin "2") (pinfunction "2_2") (pintype "passive"))
      (node (ref "R24") (pin "1") (pinfunction "1_1") (pintype "passive"))
      (node (ref "R25") (pin "1") (pinfunction "1_1") (pintype "passive"))
    )
    (net (code "61") (name "Net-(IC6B--IN)") (class "Default")
      (node (ref "C46") (pin "1") (pinfunction "1_1") (pintype "passive"))
      (node (ref "IC6") (pin "6") (pinfunction "-IN_6") (pintype "input"))
      (node (ref "R30") (pin "1") (pinfunction "1_1") (pintype "passive"))
      (node (ref "R31") (pin "2") (pinfunction "2_2") (pintype "passive"))
      (node (ref "R40") (pin "1") (pinfunction "1_1") (pintype "passive"))
    )
    (net (code "62") (name "Net-(IC6C--IN)") (class "Default")
      (node (ref "C47") (pin "1") (pinfunction "1_1") (pintype "passive"))
      (node (ref "IC6") (pin "9") (pinfunction "-IN_9") (pintype "input"))
      (node (ref "R32") (pin "2") (pinfunction "2_2") (pintype "passive"))
      (node (ref "R33") (pin "1") (pinfunction "1_1") (pintype "passive"))
      (node (ref "R41") (pin "1") (pinfunction "1_1") (pintype "passive"))
    )
    (net (code "63") (name "Net-(IC6D--IN)") (class "Default")
      (node (ref "C39") (pin "1") (pinfunction "1_1") (pintype "passive"))
      (node (ref "IC6") (pin "13") (pinfunction "-IN_13") (pintype "input"))
      (node (ref "R14") (pin "1") (pinfunction "1_1") (pintype "passive"))
      (node (ref "R18") (pin "2") (pinfunction "2_2") (pintype "passive"))
      (node (ref "R26") (pin "1") (pinfunction "1_1") (pintype "passive"))
    )
    (net (code "64") (name "Net-(IC7A--IN)") (class "Default")
      (node (ref "C40") (pin "1") (pinfunction "1_1") (pintype "passive"))
      (node (ref "IC7") (pin "2") (pinfunction "-IN_2") (pintype "input"))
      (node (ref "R15") (pin "1") (pinfunction "1_1") (pintype "passive"))
      (node (ref "R19") (pin "2") (pinfunction "2_2") (pintype "passive"))
      (node (ref "R23") (pin "1") (pinfunction "1_1") (pintype "passive"))
    )
    (net (code "65") (name "Net-(IC7B--IN)") (class "Default")
      (node (ref "C48") (pin "1") (pinfunction "1_1") (pintype "passive"))
      (node (ref "IC7") (pin "6") (pinfunction "-IN_6") (pintype "input"))
      (node (ref "R29") (pin "1") (pinfunction "1_1") (pintype "passive"))
      (node (ref "R34") (pin "2") (pinfunction "2_2") (pintype "passive"))
      (node (ref "R38") (pin "1") (pinfunction "1_1") (pintype "passive"))
    )
    (net (code "66") (name "Net-(IC7C--IN)") (class "Default")
      (node (ref "C49") (pin "1") (pinfunction "1_1") (pintype "passive"))
      (node (ref "IC7") (pin "9") (pinfunction "-IN_9") (pintype "input"))
      (node (ref "R35") (pin "2") (pinfunction "2_2") (pintype "passive"))
      (node (ref "R36") (pin "1") (pinfunction "1_1") (pintype "passive"))
      (node (ref "R39") (pin "1") (pinfunction "1_1") (pintype "passive"))
    )
    (net (code "67") (name "Net-(IC7D--IN)") (class "Default")
      (node (ref "C41") (pin "1") (pinfunction "1_1") (pintype "passive"))
      (node (ref "IC7") (pin "13") (pinfunction "-IN_13") (pintype "input"))
      (node (ref "R13") (pin "1") (pinfunction "1_1") (pintype "passive"))
      (node (ref "R20") (pin "2") (pinfunction "2_2") (pintype "passive"))
      (node (ref "R27") (pin "1") (pinfunction "1_1") (pintype "passive"))
    )
    (net (code "68") (name "Net-(IC8A--IN)") (class "Default")
      (node (ref "C42") (pin "1") (pinfunction "1_1") (pintype "passive"))
      (node (ref "IC8") (pin "2") (pinfunction "-IN_2") (pintype "input"))
      (node (ref "R21") (pin "1") (pinfunction "1_1") (pintype "passive"))
      (node (ref "R22") (pin "2") (pinfunction "2_2") (pintype "passive"))
    )
    (net (code "69") (name "Net-(IC8A-OUT)") (class "Default")
      (node (ref "C42") (pin "2") (pinfunction "2_2") (pintype "passive"))
      (node (ref "IC8") (pin "1") (pinfunction "OUT_1") (pintype "output"))
      (node (ref "R22") (pin "1") (pinfunction "1_1") (pintype "passive"))
      (node (ref "R46") (pin "2") (pinfunction "2_2") (pintype "passive"))
    )
    (net (code "70") (name "Net-(IC8B--IN)") (class "Default")
      (node (ref "C43") (pin "1") (pinfunction "1_1") (pintype "passive"))
      (node (ref "IC8") (pin "6") (pinfunction "-IN_6") (pintype "input"))
      (node (ref "R16") (pin "1") (pinfunction "1_1") (pintype "passive"))
      (node (ref "R28") (pin "2") (pinfunction "2_2") (pintype "passive"))
    )
    (net (code "71") (name "Net-(IC8B-OUT)") (class "Default")
      (node (ref "C43") (pin "2") (pinfunction "2_2") (pintype "passive"))
      (node (ref "IC8") (pin "7") (pinfunction "OUT_7") (pintype "output"))
      (node (ref "R28") (pin "1") (pinfunction "1_1") (pintype "passive"))
      (node (ref "R47") (pin "2") (pinfunction "2_2") (pintype "passive"))
    )
    (net (code "72") (name "Net-(J1-3)") (class "Default")
      (node (ref "C55") (pin "1") (pinfunction "1_1") (pintype "passive"))
      (node (ref "J1") (pin "P3") (pinfunction "3_P3") (pintype "passive"))
      (node (ref "R40") (pin "2") (pinfunction "2_2") (pintype "passive"))
    )
    (net (code "73") (name "Net-(J2-2)") (class "Default")
      (node (ref "J2") (pin "P2") (pinfunction "2_P2") (pintype "passive"))
      (node (ref "R48") (pin "1") (pinfunction "1_1") (pintype "passive"))
    )
    (net (code "74") (name "Net-(J2-3)") (class "Default")
      (node (ref "C56") (pin "1") (pinfunction "1_1") (pintype "passive"))
      (node (ref "J2") (pin "P3") (pinfunction "3_P3") (pintype "passive"))
      (node (ref "R41") (pin "2") (pinfunction "2_2") (pintype "passive"))
    )
    (net (code "75") (name "Net-(J3-2)") (class "Default")
      (node (ref "J3") (pin "P2") (pinfunction "2_P2") (pintype "passive"))
      (node (ref "R49") (pin "1") (pinfunction "1_1") (pintype "passive"))
    )
    (net (code "76") (name "Net-(J3-3)") (class "Default")
      (node (ref "C57") (pin "1") (pinfunction "1_1") (pintype "passive"))
      (node (ref "J3") (pin "P3") (pinfunction "3_P3") (pintype "passive"))
      (node (ref "R15") (pin "2") (pinfunction "2_2") (pintype "passive"))
    )
    (net (code "77") (name "Net-(J4-2)") (class "Default")
      (node (ref "J4") (pin "P2") (pinfunction "2_P2") (pintype "passive"))
      (node (ref "R45") (pin "1") (pinfunction "1_1") (pintype "passive"))
    )
    (net (code "78") (name "Net-(J4-3)") (class "Default")
      (node (ref "C54") (pin "1") (pinfunction "1_1") (pintype "passive"))
      (node (ref "J4") (pin "P3") (pinfunction "3_P3") (pintype "passive"))
      (node (ref "R39") (pin "2") (pinfunction "2_2") (pintype "passive"))
    )
    (net (code "79") (name "Net-(J5-3)") (class "Default")
      (node (ref "C58") (pin "1") (pinfunction "1_1") (pintype "passive"))
      (node (ref "J5") (pin "P3") (pinfunction "3_P3") (pintype "passive"))
      (node (ref "R13") (pin "2") (pinfunction "2_2") (pintype "passive"))
    )
    (net (code "80") (name "Net-(J6-2)") (class "Default")
      (node (ref "J6") (pin "P2") (pinfunction "2_P2") (pintype "passive"))
      (node (ref "R50") (pin "2") (pinfunction "2_2") (pintype "passive"))
    )
    (net (code "81") (name "Net-(J6-3)") (class "Default")
      (node (ref "C59") (pin "1") (pinfunction "1_1") (pintype "passive"))
      (node (ref "J6") (pin "P3") (pinfunction "3_P3") (pintype "passive"))
      (node (ref "R24") (pin "2") (pinfunction "2_2") (pintype "passive"))
    )
    (net (code "82") (name "Net-(J7-2)") (class "Default")
      (node (ref "J7") (pin "P2") (pinfunction "2_P2") (pintype "passive"))
      (node (ref "R51") (pin "1") (pinfunction "1_1") (pintype "passive"))
    )
    (net (code "83") (name "Net-(J7-3)") (class "Default")
      (node (ref "C61") (pin "1") (pinfunction "1_1") (pintype "passive"))
      (node (ref "J7") (pin "P3") (pinfunction "3_P3") (pintype "passive"))
      (node (ref "R14") (pin "2") (pinfunction "2_2") (pintype "passive"))
    )
    (net (code "84") (name "Net-(J8-3)") (class "Default")
      (node (ref "C60") (pin "1") (pinfunction "1_1") (pintype "passive"))
      (node (ref "J8") (pin "P3") (pinfunction "3_P3") (pintype "passive"))
      (node (ref "R38") (pin "2") (pinfunction "2_2") (pintype "passive"))
    )
    (net (code "85") (name "Net-(J9-3)") (class "Default")
      (node (ref "J9") (pin "P3") (pinfunction "3_P3") (pintype "passive"))
      (node (ref "R46") (pin "1") (pinfunction "1_1") (pintype "passive"))
    )
    (net (code "86") (name "Net-(J10-3)") (class "Default")
      (node (ref "J10") (pin "P3") (pinfunction "3_P3") (pintype "passive"))
      (node (ref "R47") (pin "1") (pinfunction "1_1") (pintype "passive"))
    )
    (net (code "87") (name "Net-(JP5-Pad1)") (class "Default")
      (node (ref "JP5") (pin "1") (pinfunction "1_1") (pintype "passive"))
      (node (ref "R9") (pin "1") (pinfunction "1_1") (pintype "passive"))
    )
    (net (code "88") (name "Net-(JP5-Pad2)") (class "Default")
      (node (ref "JP5") (pin "2") (pinfunction "2_2") (pintype "passive"))
      (node (ref "R10") (pin "1") (pinfunction "1_1") (pintype "passive"))
    )
    (net (code "89") (name "Net-(Q1B-2)") (class "Default")
      (node (ref "C14") (pin "2") (pinfunction "2_2") (pintype "passive"))
      (node (ref "Q1") (pin "3") (pinfunction "2_3") (pintype "passive"))
      (node (ref "R5") (pin "2") (pinfunction "2_2") (pintype "passive"))
    )
    (net (code "90") (name "RESET") (class "Default")
      (node (ref "C15") (pin "1") (pinfunction "1_1") (pintype "passive"))
      (node (ref "IC4") (pin "7") (pinfunction "NRST_7") (pintype "bidirectional"))
      (node (ref "JP6") (pin "4") (pinfunction "4_4") (pintype "passive"))
      (node (ref "R4") (pin "2") (pinfunction "2_2") (pintype "passive"))
    )
    (net (code "91") (name "RX") (class "Default")
      (node (ref "IC4") (pin "46") (pinfunction "PB9/SPI2_NSS/I2S2_WS/I2C1_SDA/USART3_RX/CAN_TX/TIM4_CH4_46") (pintype "bidirectional"))
      (node (ref "R9") (pin "2") (pinfunction "2_2") (pintype "passive"))
    )
    (net (code "92") (name "SWCLK") (class "Default")
      (node (ref "IC4") (pin "37") (pinfunction "PA14/I2C1_SDA/JTCK-SWCLK_37") (pintype "bidirectional"))
      (node (ref "JP6") (pin "3") (pinfunction "3_3") (pintype "passive"))
    )
    (net (code "93") (name "SWDIO") (class "Default")
      (node (ref "IC4") (pin "34") (pinfunction "PA13/SPI1_MISO/I2S1_MCK/USART3_CTS/TIM4_CH3/TIM5_CH4/JTMS-SWDIO_34") (pintype "bidirectional"))
      (node (ref "JP6") (pin "2") (pinfunction "2_2") (pintype "passive"))
    )
    (net (code "94") (name "SW_1") (class "Default")
      (node (ref "IC4") (pin "43") (pinfunction "PB7/I2C1_SDA/USART1_RX/TIM4_CH2_43") (pintype "bidirectional"))
      (node (ref "SW1") (pin "3") (pinfunction "3_3") (pintype "passive"))
      (node (ref "SW1") (pin "4") (pinfunction "4_4") (pintype "passive"))
    )
    (net (code "95") (name "SW_2") (class "Default")
      (node (ref "IC4") (pin "42") (pinfunction "PB6/I2C1_SCL/USART1_TX/TIM4_CH1_42") (pintype "bidirectional"))
      (node (ref "SW2") (pin "3") (pinfunction "3_3") (pintype "passive"))
      (node (ref "SW2") (pin "4") (pinfunction "4_4") (pintype "passive"))
    )
    (net (code "96") (name "TIMBRE_ATT") (class "Default")
      (node (ref "C53") (pin "1") (pinfunction "1_1") (pintype "passive"))
      (node (ref "IC4") (pin "16") (pinfunction "PA6/SPI1_MISO/I2S1_MCK/TIM3_CH1/ADC_IN6/DAC2_OUT1_16") (pintype "bidirectional"))
      (node (ref "R42") (pin "P$2") (pinfunction "S_P$2") (pintype "passive"))
    )
    (net (code "97") (name "TIMBRE_POT") (class "Default")
      (node (ref "C32") (pin "1") (pinfunction "1_1") (pintype "passive"))
      (node (ref "IC4") (pin "13") (pinfunction "PA3/SPI3_MOSI/I2S3_SD/USART2_RX/TIM2_CH4/TIM5_CH4/ADC_IN3_13") (pintype "bidirectional"))
      (node (ref "R7") (pin "P$2") (pinfunction "S_P$2") (pintype "passive"))
    )
    (net (code "98") (name "TX") (class "Default")
      (node (ref "IC4") (pin "45") (pinfunction "PB8/SPI2_SCK/I2S2_CK/I2C1_SCL/USART3_TX/CAN_RX/TIM4_CH3_45") (pintype "bidirectional"))
      (node (ref "R10") (pin "2") (pinfunction "2_2") (pintype "passive"))
    )
    (net (code "99") (name "VCC") (class "Default")
      (node (ref "C37") (pin "1") (pinfunction "1_1") (pintype "passive"))
      (node (ref "C4") (pin "+") (pinfunction "+_+") (pintype "passive"))
      (node (ref "IC8") (pin "8") (pinfunction "V+_8") (pintype "power_in"))
      (node (ref "L2") (pin "1") (pinfunction "1_1") (pintype "passive"))
    )
    (net (code "100") (name "VEE") (class "Default")
      (node (ref "C45") (pin "2") (pinfunction "2_2") (pintype "passive"))
      (node (ref "C5") (pin "-") (pinfunction "-_-") (pintype "passive"))
      (node (ref "IC8") (pin "4") (pinfunction "V-_4") (pintype "power_in"))
      (node (ref "L3") (pin "1") (pinfunction "1_1") (pintype "passive"))
      (node (ref "R37") (pin "1") (pinfunction "1_1") (pintype "passive"))
    )
    (net (code "101") (name "unconnected-(IC2-SOUT-Pad22)") (class "Default")
      (node (ref "IC2") (pin "22") (pinfunction "SOUT_22") (pintype "bidirectional"))
    )
    (net (code "102") (name "unconnected-(IC4-PA15{slash}SPI1_NSS{slash}I2S1_WS{slash}SPI3_NSS{slash}I2S3_WS{slash}I2C1_SCL{slash}TIM2_CH1_ETR{slash}JTDI-Pad38)") (class "Default")
      (node (ref "IC4") (pin "38") (pinfunction "PA15/SPI1_NSS/I2S1_WS/SPI3_NSS/I2S3_WS/I2C1_SCL/TIM2_CH1_ETR/JTDI_38") (pintype "bidirectional"))
    )
    (net (code "103") (name "unconnected-(IC4-PB3{slash}SPI1_SCK{slash}I2S1_CK{slash}SPI3_SCK{slash}I2S3_CK{slash}USART2_TX{slash}TIM2_CH2{slash}JTDO{slash}SPI3_SCK{slash}JTDO-Pad39)") (class "Default")
      (node (ref "IC4") (pin "39") (pinfunction "PB3/SPI1_SCK/I2S1_CK/SPI3_SCK/I2S3_CK/USART2_TX/TIM2_CH2/JTDO/SPI3_SCK/JTDO_39") (pintype "bidirectional"))
    )
    (net (code "104") (name "unconnected-(IC4-PB4{slash}SPI1_MISO{slash}I2S1_MCK{slash}SPI3_MISO{slash}I2S3_MCK{slash}USART2_RX{slash}TIM3_CH1{slash}NJTRST-Pad40)") (class "Default")
      (node (ref "IC4") (pin "40") (pinfunction "PB4/SPI1_MISO/I2S1_MCK/SPI3_MISO/I2S3_MCK/USART2_RX/TIM3_CH1/NJTRST_40") (pintype "bidirectional"))
    )
    (net (code "105") (name "unconnected-(IC4-PB5{slash}SPI1_MOSI{slash}I2S1_SD{slash}SPI3_MOSI{slash}I2S3_SD{slash}I2C1_SMBAI{slash}USART2_CK{slash}TIM3_CH2-Pad41)") (class "Default")
      (node (ref "IC4") (pin "41") (pinfunction "PB5/SPI1_MOSI/I2S1_SD/SPI3_MOSI/I2S3_SD/I2C1_SMBAI/USART2_CK/TIM3_CH2_41") (pintype "bidirectional"))
    )
    (net (code "106") (name "unconnected-(IC4-PC13{slash}TIMESTAMP{slash}RTC_TAMPER1-Pad2)") (class "Default")
      (node (ref "IC4") (pin "2") (pinfunction "PC13/TIMESTAMP/RTC_TAMPER1_2") (pintype "bidirectional"))
    )
    (net (code "107") (name "unconnected-(IC4-PC14{slash}OSC32_IN-Pad3)") (class "Default")
      (node (ref "IC4") (pin "3") (pinfunction "PC14/OSC32_IN_3") (pintype "bidirectional"))
    )
    (net (code "108") (name "unconnected-(IC4-PC15{slash}OSC32_OUT-Pad4)") (class "Default")
      (node (ref "IC4") (pin "4") (pinfunction "PC15/OSC32_OUT_4") (pintype "bidirectional"))
    )
    (net (code "109") (name "unconnected-(J9-2-PadP2)") (class "Default")
      (node (ref "J9") (pin "P2") (pinfunction "2_P2") (pintype "passive"))
    )
    (net (code "110") (name "unconnected-(J10-2-PadP2)") (class "Default")
      (node (ref "J10") (pin "P2") (pinfunction "2_P2") (pintype "passive"))
    )
  )
)
